# oresat-c3-prototype.net
KiCad netlist of a schematic drawn in EAGLE
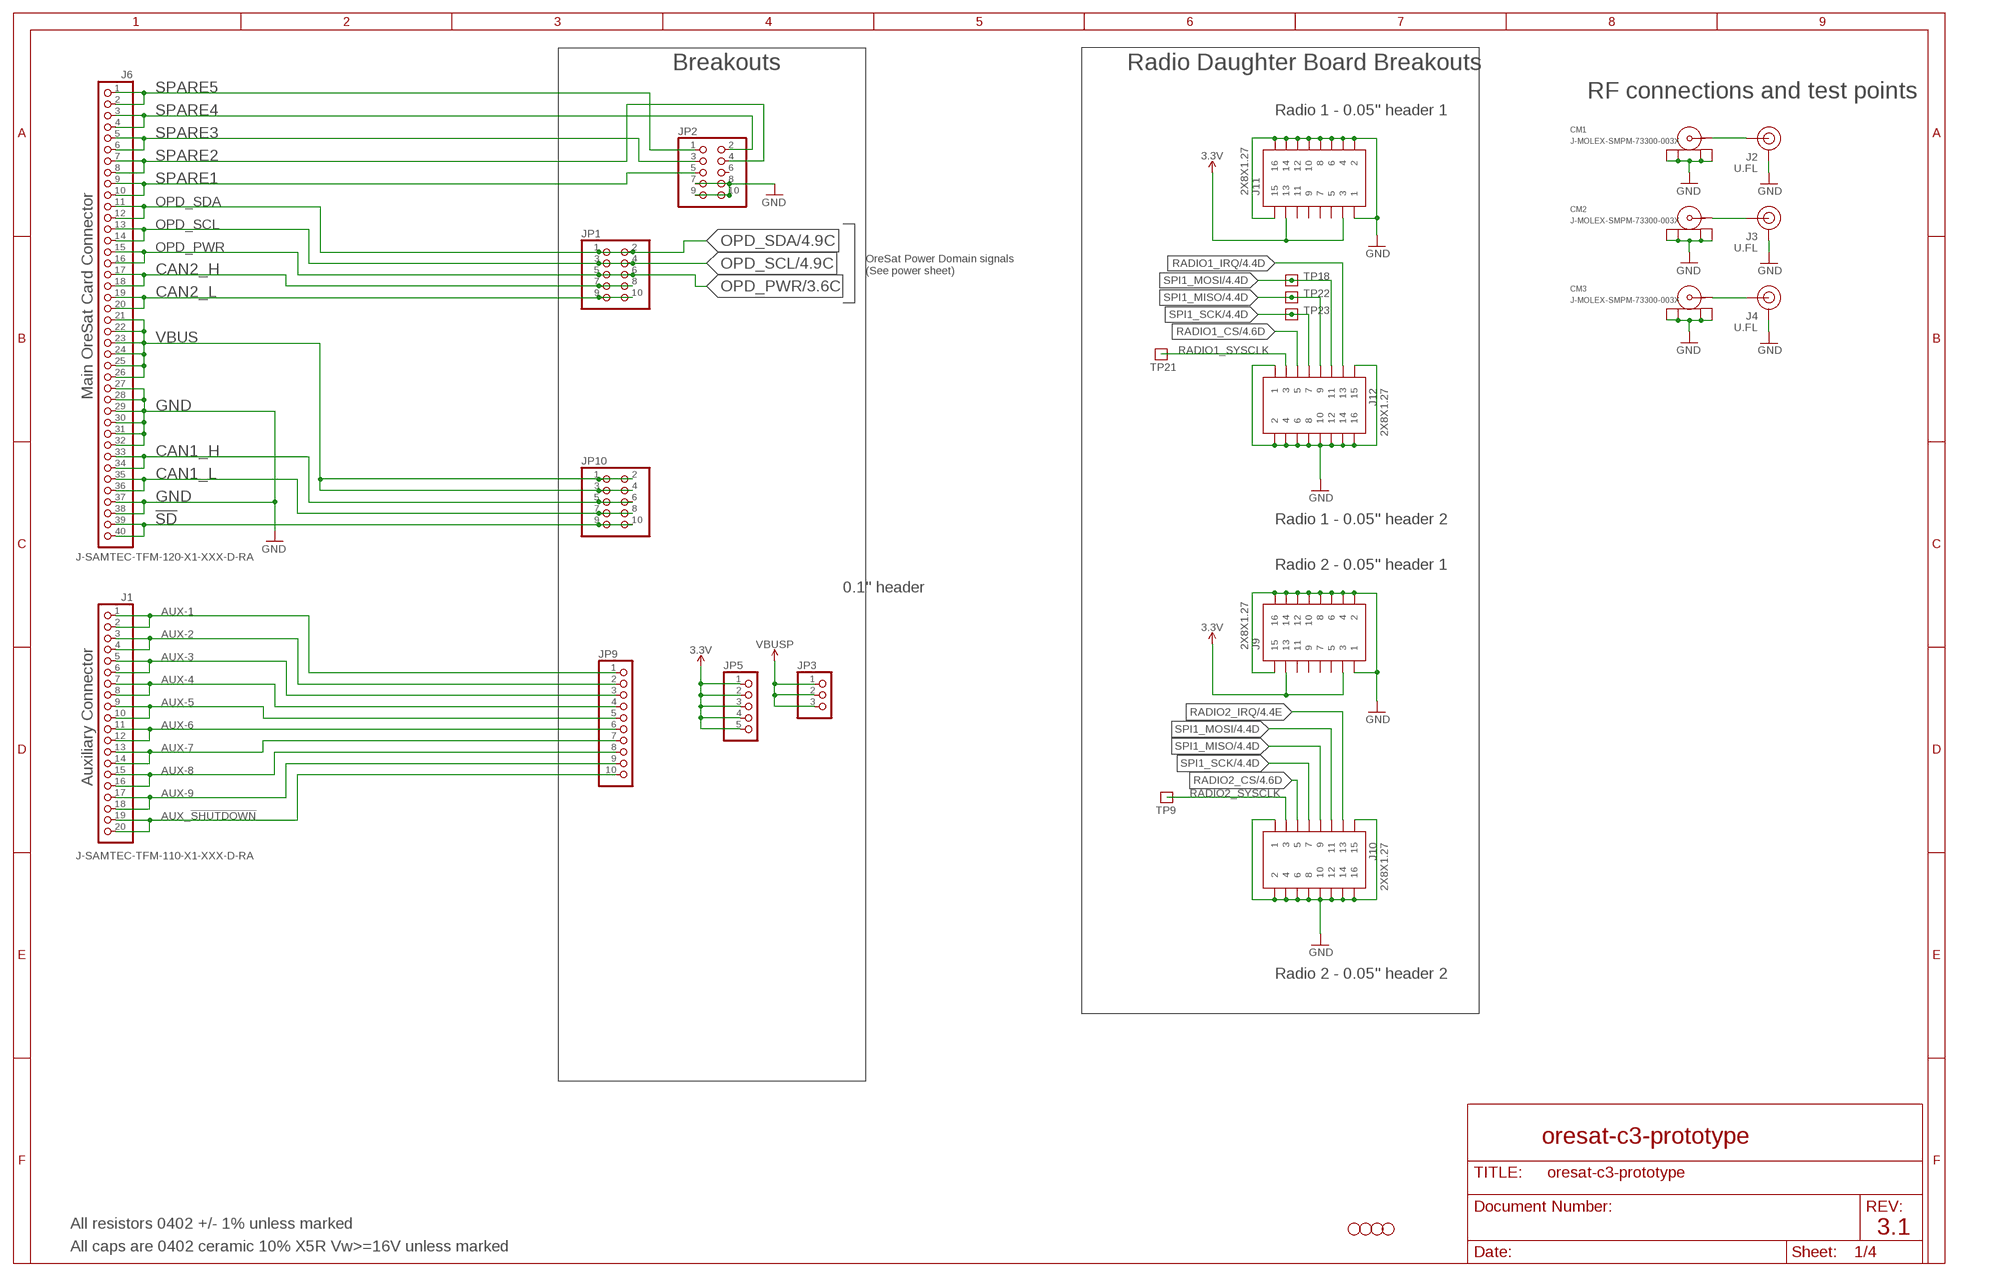
[diagram p0: schematic, sheet 1]
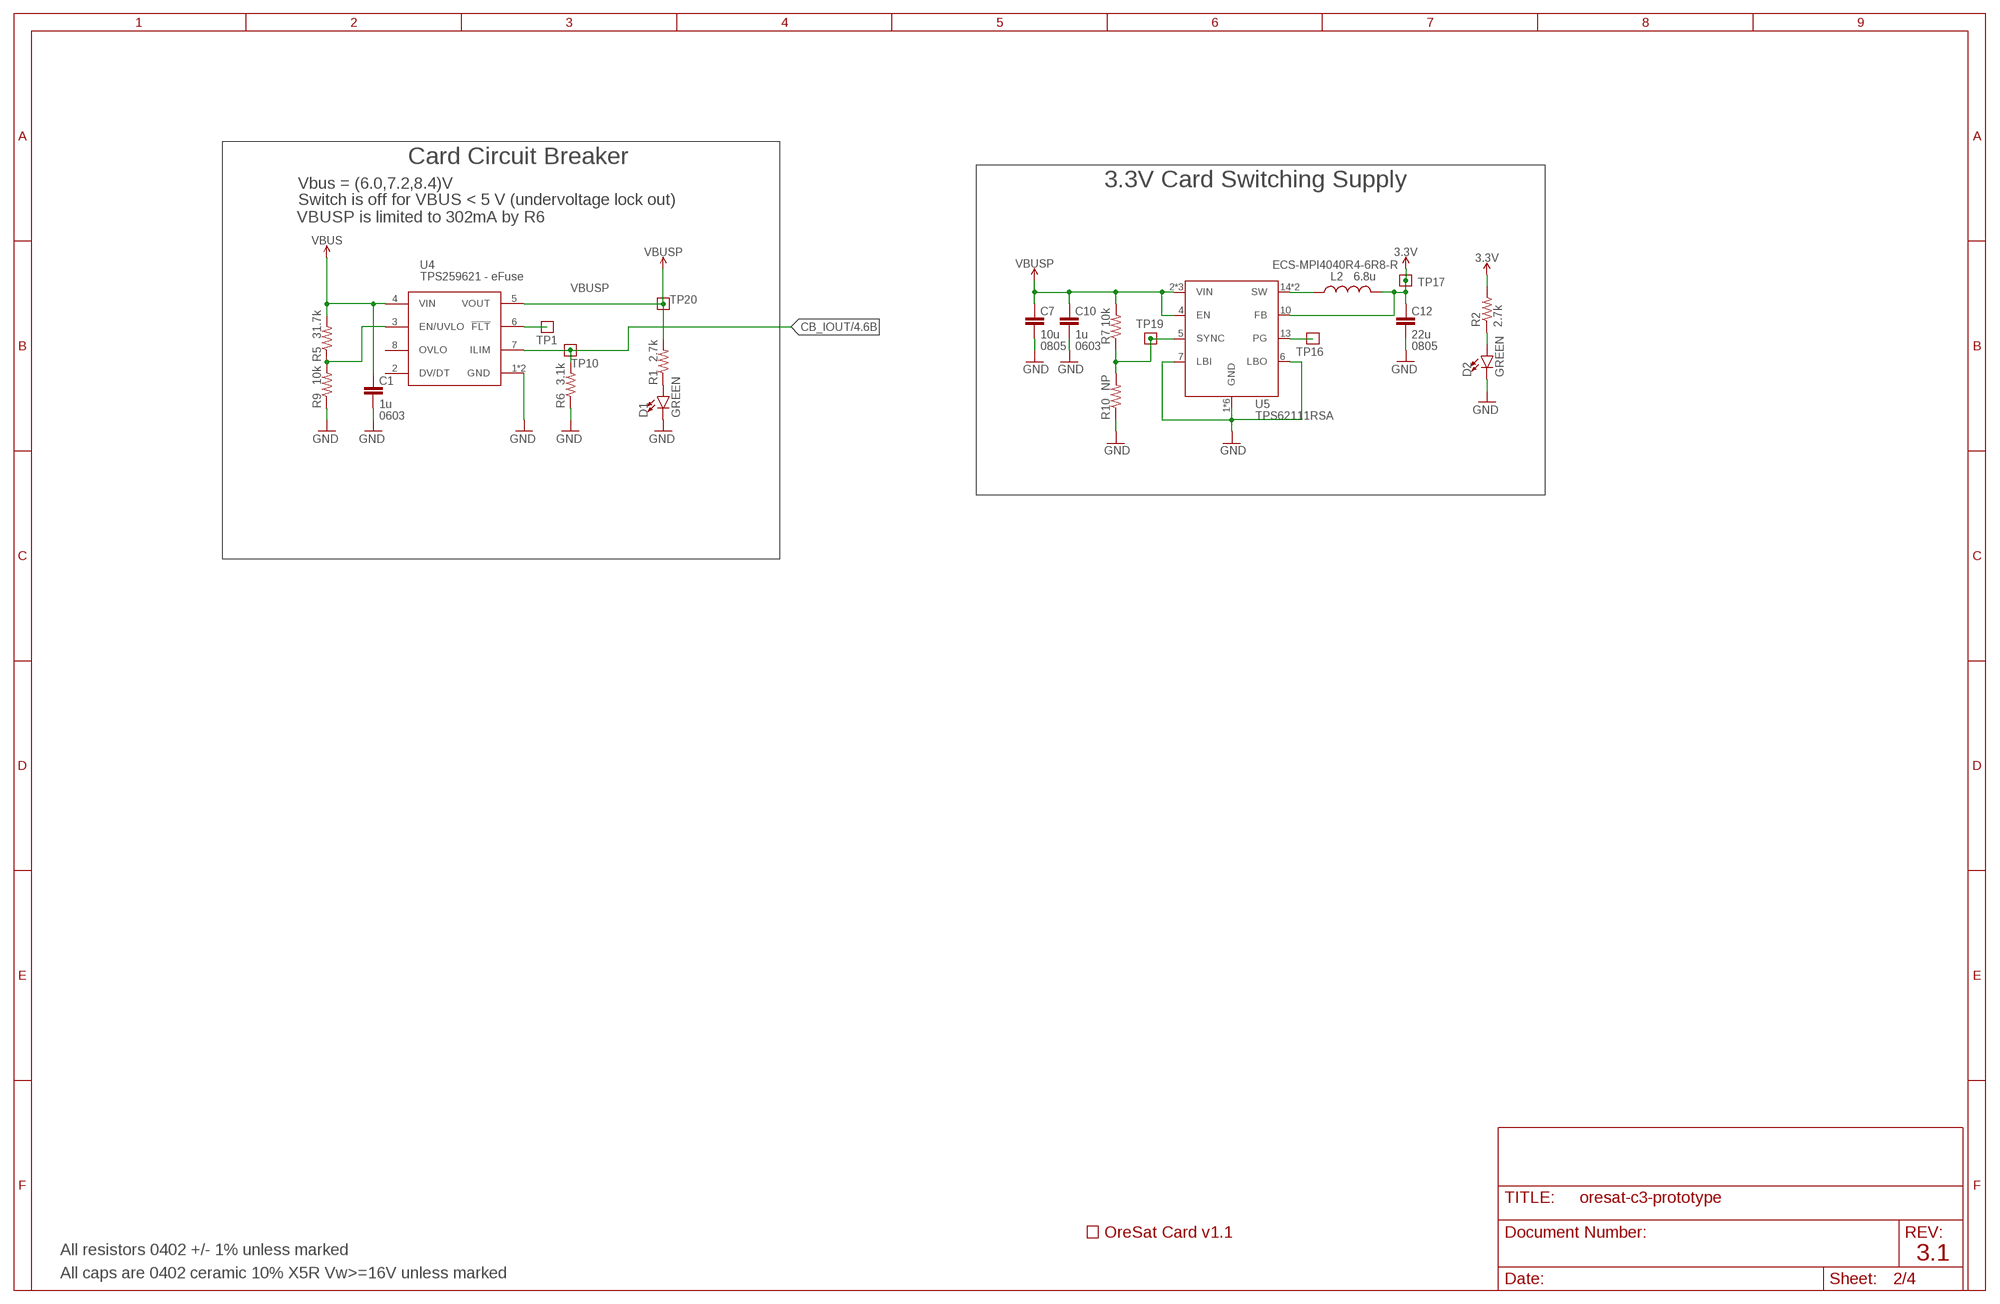
[diagram p1: schematic, sheet 2]
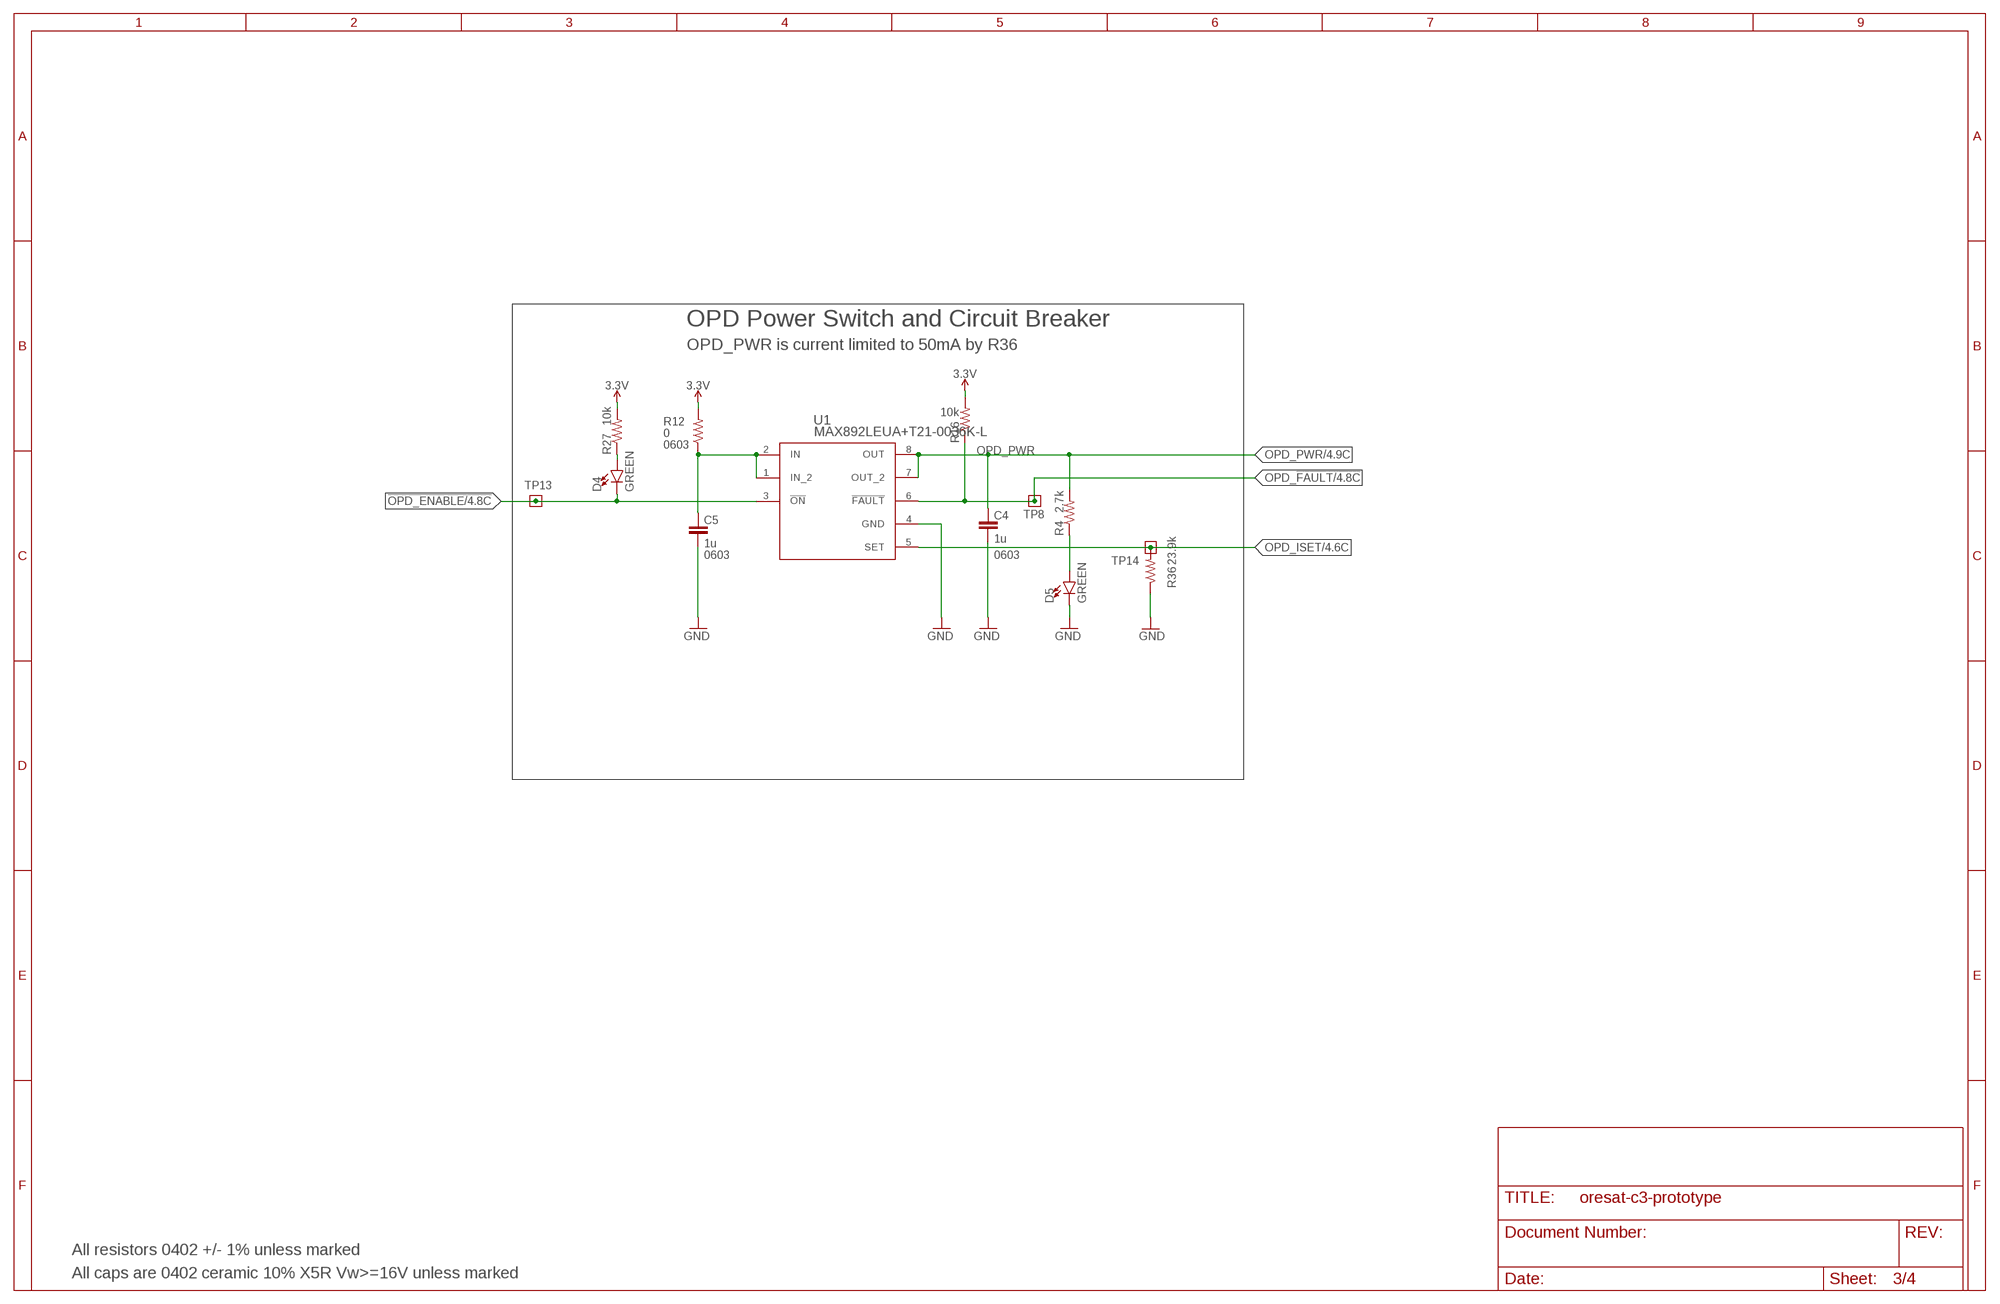
[diagram p2: schematic, sheet 3]
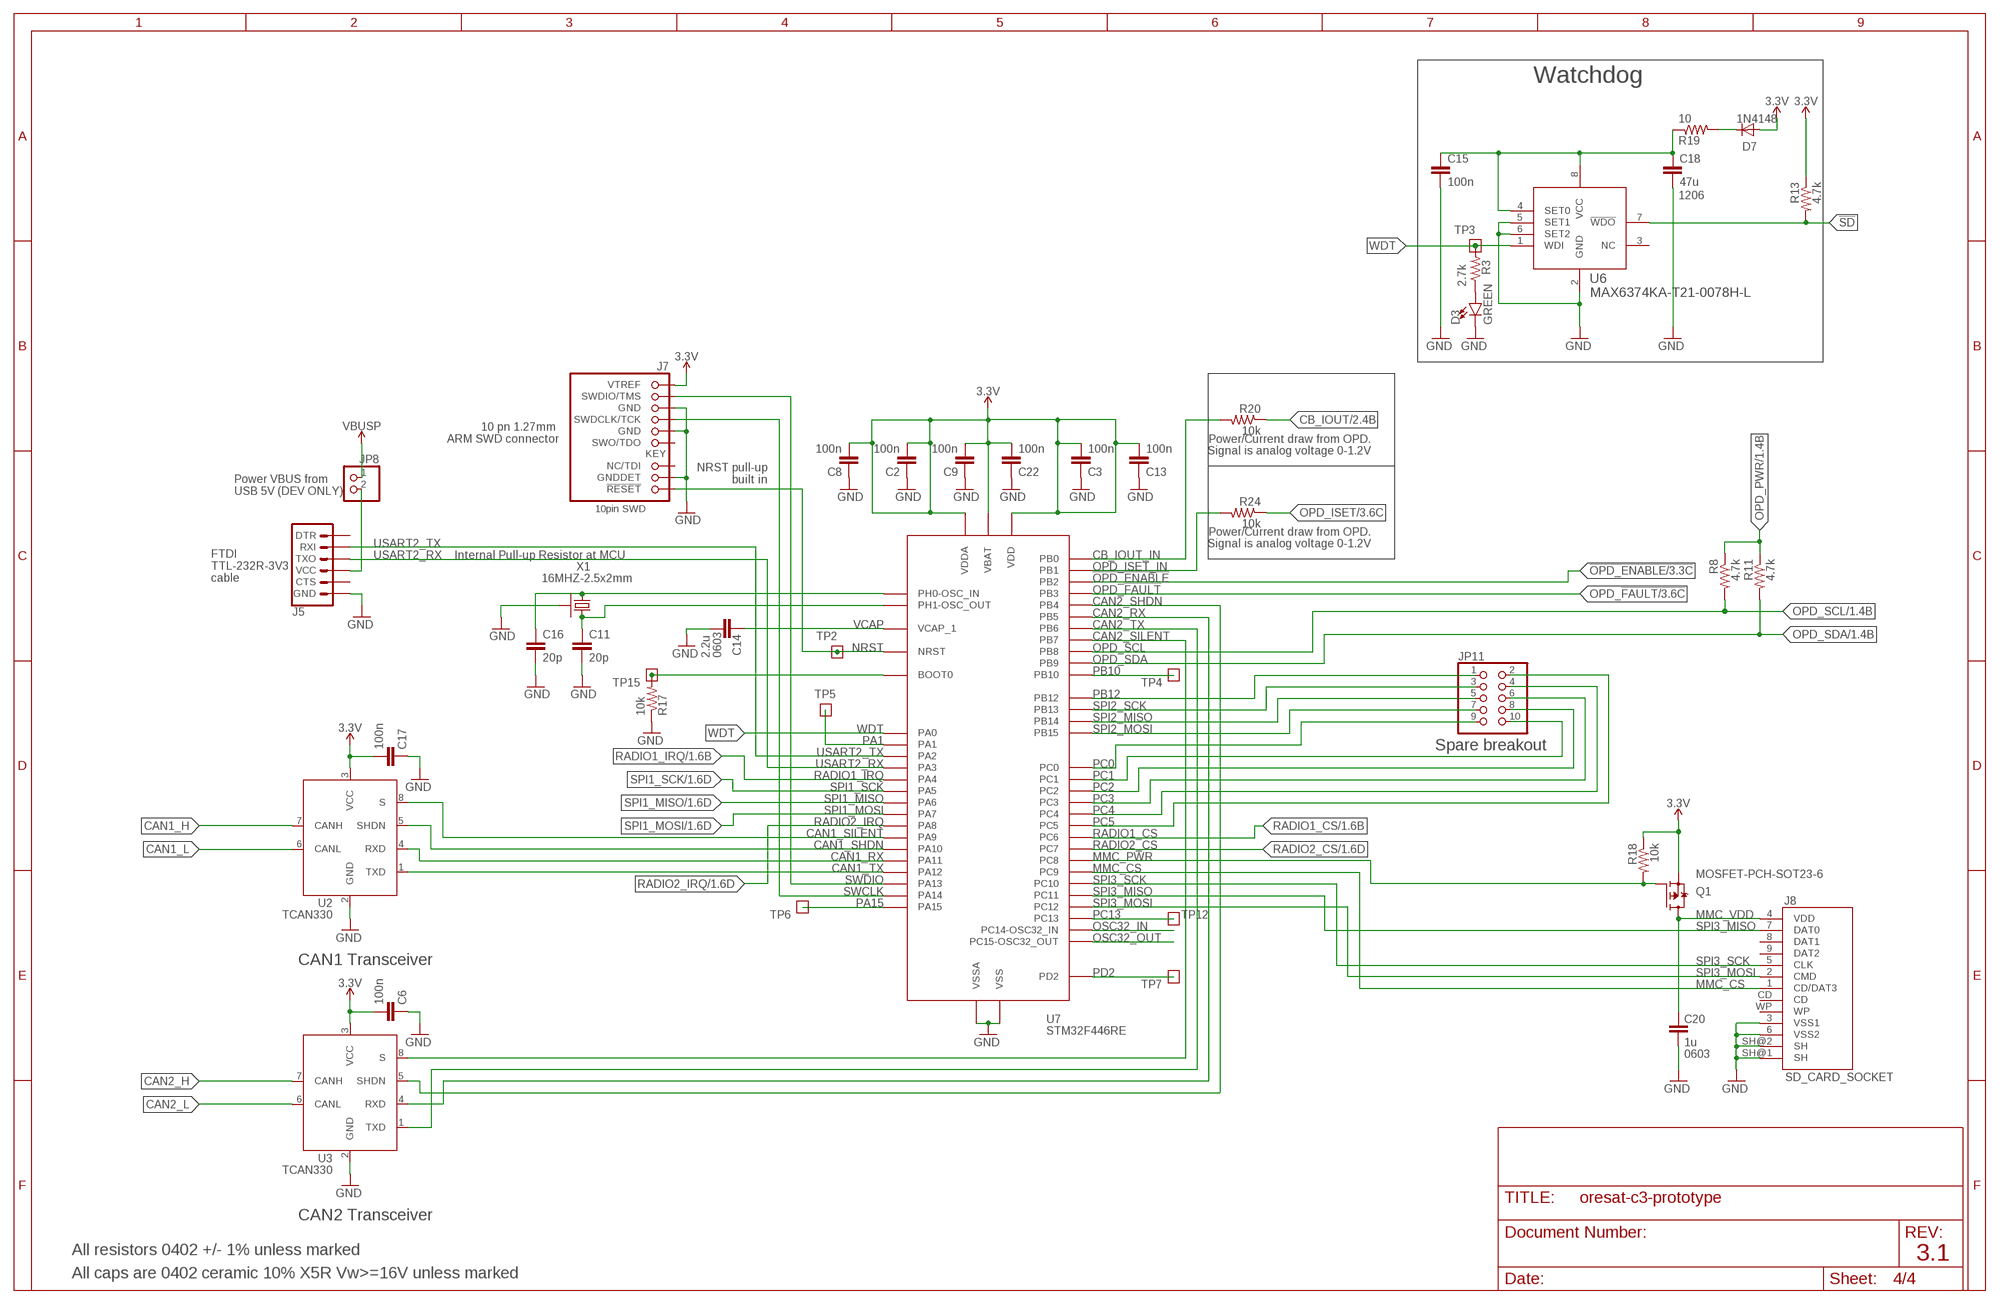
[diagram p3: schematic, sheet 4]

(export (version "E")
  (design (tool "Eeschema 10.0.6"))
  (components
    (comp (ref "C4")
      (value "1u")
      (footprint "eagle-import:.0603-B-NOSILK")
      (fields (field (name "MFR") "Samsung") (field (name "MPN") "CL05B104KO5NNNC"))
      (libsource (lib "eagle-import") (part "C-EU0603-B-NOSILK"))
    )
    (comp (ref "C5")
      (value "1u")
      (footprint "eagle-import:.0603-B-NOSILK")
      (fields (field (name "MFR") "Samsung") (field (name "MPN") "CL05B104KO5NNNC"))
      (libsource (lib "eagle-import") (part "C-EU0603-B-NOSILK"))
    )
    (comp (ref "D4")
      (value "GREEN")
      (footprint "eagle-import:LED-0603")
      (libsource (lib "eagle-import") (part "LED-GREEN0603"))
    )
    (comp (ref "D5")
      (value "GREEN")
      (footprint "eagle-import:LED-0603")
      (libsource (lib "eagle-import") (part "LED-GREEN0603"))
    )
    (comp (ref "R4")
      (value "2.7k")
      (footprint "eagle-import:.0402-B-NOSILK")
      (fields (field (name "MFR") "Samsung") (field (name "MPN") "RC1005F6653CS"))
      (libsource (lib "eagle-import") (part "R-US_0402-B-NOSILK"))
    )
    (comp (ref "R12")
      (value "0")
      (footprint "eagle-import:.0603-B-NOSILK")
      (fields (field (name "MFR") "Samsung") (field (name "MPN") "RC1005F6653CS"))
      (libsource (lib "eagle-import") (part "R-US_0603-B-NOSILK"))
    )
    (comp (ref "R16")
      (value "10k")
      (footprint "eagle-import:.0402-B-NOSILK")
      (fields (field (name "MFR") "Samsung") (field (name "MPN") "RC1005F6653CS"))
      (libsource (lib "eagle-import") (part "R-US_0402-B-NOSILK"))
    )
    (comp (ref "R27")
      (value "10k")
      (footprint "eagle-import:.0402-B-NOSILK")
      (fields (field (name "MFR") "Samsung") (field (name "MPN") "RC1005F6653CS"))
      (libsource (lib "eagle-import") (part "R-US_0402-B-NOSILK"))
    )
    (comp (ref "R36")
      (value "23.9k")
      (footprint "eagle-import:.0402-B-NOSILK")
      (fields (field (name "MFR") "Samsung") (field (name "MPN") "RC1005F6653CS"))
      (libsource (lib "eagle-import") (part "R-US_0402-B-NOSILK"))
    )
    (comp (ref "TP8")
      (value "TEST-POINT")
      (footprint "eagle-import:2MM-TEST-POINT")
      (libsource (lib "eagle-import") (part "TEST-POINT"))
    )
    (comp (ref "TP13")
      (value "TEST-POINT")
      (footprint "eagle-import:2MM-TEST-POINT")
      (libsource (lib "eagle-import") (part "TEST-POINT"))
    )
    (comp (ref "TP14")
      (value "TEST-POINT")
      (footprint "eagle-import:2MM-TEST-POINT")
      (libsource (lib "eagle-import") (part "TEST-POINT"))
    )
    (comp (ref "U1")
      (value "MAX892LEUA+T21-0036K-L")
      (footprint "eagle-import:21-0036K-L")
      (fields (field (name "MANUFACTURER_PART_NUMBER") "MAX892LEUA+T"))
      (libsource (lib "eagle-import") (part "MAX892LEUA+T21-0036K-L"))
    )
    (comp (ref "C2")
      (value "100n")
      (footprint "eagle-import:.0402-B-NOSILK")
      (fields (field (name "MFR") "Samsung") (field (name "MPN") "CL05B104KO5NNNC"))
      (libsource (lib "eagle-import") (part "C-EU0402-B-NOSILK"))
    )
    (comp (ref "C3")
      (value "100n")
      (footprint "eagle-import:.0402-B-NOSILK")
      (fields (field (name "MFR") "Samsung") (field (name "MPN") "CL05B104KO5NNNC"))
      (libsource (lib "eagle-import") (part "C-EU0402-B-NOSILK"))
    )
    (comp (ref "C6")
      (value "100n")
      (footprint "eagle-import:.0402-B-NOSILK")
      (fields (field (name "MFR") "Samsung") (field (name "MPN") "CL05B104KO5NNNC"))
      (libsource (lib "eagle-import") (part "C-EU0402-B-NOSILK"))
    )
    (comp (ref "C8")
      (value "100n")
      (footprint "eagle-import:.0402-B-NOSILK")
      (fields (field (name "MFR") "Samsung") (field (name "MPN") "CL05B104KO5NNNC"))
      (libsource (lib "eagle-import") (part "C-EU0402-B-NOSILK"))
    )
    (comp (ref "C9")
      (value "100n")
      (footprint "eagle-import:.0402-B-NOSILK")
      (fields (field (name "MFR") "Samsung") (field (name "MPN") "CL05B104KO5NNNC"))
      (libsource (lib "eagle-import") (part "C-EU0402-B-NOSILK"))
    )
    (comp (ref "C11")
      (value "20p")
      (footprint "eagle-import:.0402-B-NOSILK")
      (fields (field (name "MFR") "Samsung") (field (name "MPN") "CL05C200JB51PNC"))
      (libsource (lib "eagle-import") (part "rcl_custom_C-EU0402-B-NOSILK"))
    )
    (comp (ref "C13")
      (value "100n")
      (footprint "eagle-import:.0402-B-NOSILK")
      (fields (field (name "MFR") "Samsung") (field (name "MPN") "CL05B104KO5NNNC"))
      (libsource (lib "eagle-import") (part "C-EU0402-B-NOSILK"))
    )
    (comp (ref "C14")
      (value "2.2u")
      (footprint "eagle-import:.0603-B-NOSILK")
      (fields (field (name "MFR") "Samsung") (field (name "MPN") "CL05B104KO5NNNC"))
      (libsource (lib "eagle-import") (part "C-EU0603-B-NOSILK"))
    )
    (comp (ref "C15")
      (value "100n")
      (footprint "eagle-import:.0402-B-NOSILK")
      (fields (field (name "MFR") "Samsung") (field (name "MPN") "CL05C200JB51PNC"))
      (libsource (lib "eagle-import") (part "C-EU0402-B-NOSILK"))
    )
    (comp (ref "C16")
      (value "20p")
      (footprint "eagle-import:.0402-B-NOSILK")
      (fields (field (name "MFR") "Samsung") (field (name "MPN") "CL05C200JB51PNC"))
      (libsource (lib "eagle-import") (part "C-EU0402-B-NOSILK"))
    )
    (comp (ref "C17")
      (value "100n")
      (footprint "eagle-import:.0402-B-NOSILK")
      (fields (field (name "MFR") "Samsung") (field (name "MPN") "CL05B104KO5NNNC"))
      (libsource (lib "eagle-import") (part "C-EU0402-B-NOSILK"))
    )
    (comp (ref "C18")
      (value "47u")
      (footprint "eagle-import:1206-B")
      (fields (field (name "MFR") "Samsung") (field (name "MPN") "CL05C200JB51PNC"))
      (libsource (lib "eagle-import") (part "C-EU1206-B"))
    )
    (comp (ref "C20")
      (value "1u")
      (footprint "eagle-import:.0603-B-NOSILK")
      (fields (field (name "MFR") "Samsung") (field (name "MPN") "CL05B104KO5NNNC"))
      (libsource (lib "eagle-import") (part "C-EU0603-B-NOSILK"))
    )
    (comp (ref "C22")
      (value "100n")
      (footprint "eagle-import:.0402-B-NOSILK")
      (fields (field (name "MFR") "Samsung") (field (name "MPN") "CL05B104KO5NNNC"))
      (libsource (lib "eagle-import") (part "C-EU0402-B-NOSILK"))
    )
    (comp (ref "D3")
      (value "GREEN")
      (footprint "eagle-import:LED-0603")
      (libsource (lib "eagle-import") (part "LED-GREEN0603"))
    )
    (comp (ref "D7")
      (value "1N4148")
      (footprint "eagle-import:SOD-323")
      (libsource (lib "eagle-import") (part "DIODESOD"))
    )
    (comp (ref "J5")
      (value "6_PIN_SERIAL_TARGETSILK")
      (footprint "eagle-import:6_PIN_SERIAL_TARGET_SIDE_W_SILK")
      (libsource (lib "eagle-import") (part "6_PIN_SERIAL_TARGETSILK"))
    )
    (comp (ref "J7")
      (value "FTSH-105-XX-X-DV-K")
      (footprint "eagle-import:CON10_2X5_DUK_FTSH")
      (fields (field (name "MFR") "Samtec") (field (name "MPN") "FTSH-105-01-F-DV-K"))
      (libsource (lib "eagle-import") (part "FTSH-105-XX-X-DV-K"))
    )
    (comp (ref "J8")
      (value "SD_CARD_SOCKET")
      (footprint "eagle-import:SD")
      (libsource (lib "eagle-import") (part "SD_CARD_SOCKET"))
    )
    (comp (ref "JP8")
      (value "PINHD-1X2")
      (footprint "eagle-import:1X02")
      (libsource (lib "eagle-import") (part "PINHD-1X2"))
    )
    (comp (ref "JP11")
      (value "PINHD-2X5")
      (footprint "eagle-import:2X05")
      (libsource (lib "eagle-import") (part "PINHD-2X5"))
    )
    (comp (ref "Q1")
      (value "MOSFET-PCH-SOT23-6")
      (footprint "eagle-import:SOT23-6")
      (libsource (lib "eagle-import") (part "MOSFET-PCH-SOT23-6"))
    )
    (comp (ref "R3")
      (value "2.7k")
      (footprint "eagle-import:.0402-B-NOSILK")
      (fields (field (name "MFR") "Samsung") (field (name "MPN") "RC1005F6653CS"))
      (libsource (lib "eagle-import") (part "R-US_0402-B-NOSILK"))
    )
    (comp (ref "R8")
      (value "4.7k")
      (footprint "eagle-import:.0402-B-NOSILK")
      (libsource (lib "eagle-import") (part "R-US_0402-B-NOSILK"))
    )
    (comp (ref "R11")
      (value "4.7k")
      (footprint "eagle-import:.0402-B-NOSILK")
      (libsource (lib "eagle-import") (part "R-US_0402-B-NOSILK"))
    )
    (comp (ref "R13")
      (value "4.7k")
      (footprint "eagle-import:.0402-B-NOSILK")
      (libsource (lib "eagle-import") (part "R-US_0402-B-NOSILK"))
    )
    (comp (ref "R17")
      (value "10k")
      (footprint "eagle-import:.0402-B-NOSILK")
      (fields (field (name "MFR") "Samsung") (field (name "MPN") "RC1005F6653CS"))
      (libsource (lib "eagle-import") (part "R-US_0402-B-NOSILK"))
    )
    (comp (ref "R18")
      (value "10k")
      (footprint "eagle-import:.0402-B-NOSILK")
      (libsource (lib "eagle-import") (part "R-US_0402-B-NOSILK"))
    )
    (comp (ref "R19")
      (value "10")
      (footprint "eagle-import:.0402-B-NOSILK")
      (libsource (lib "eagle-import") (part "R-US_0402-B-NOSILK"))
    )
    (comp (ref "R20")
      (value "10k")
      (footprint "eagle-import:.0402-B-NOSILK")
      (libsource (lib "eagle-import") (part "R-US_0402-B-NOSILK"))
    )
    (comp (ref "R24")
      (value "10k")
      (footprint "eagle-import:.0402-B-NOSILK")
      (libsource (lib "eagle-import") (part "R-US_0402-B-NOSILK"))
    )
    (comp (ref "TP2")
      (value "TEST-POINT")
      (footprint "eagle-import:2MM-TEST-POINT")
      (libsource (lib "eagle-import") (part "TEST-POINT"))
    )
    (comp (ref "TP3")
      (value "TEST-POINT")
      (footprint "eagle-import:2MM-TEST-POINT")
      (libsource (lib "eagle-import") (part "TEST-POINT"))
    )
    (comp (ref "TP4")
      (value "TEST-POINT")
      (footprint "eagle-import:2MM-TEST-POINT")
      (libsource (lib "eagle-import") (part "TEST-POINT"))
    )
    (comp (ref "TP5")
      (value "TEST-POINT")
      (footprint "eagle-import:2MM-TEST-POINT")
      (libsource (lib "eagle-import") (part "TEST-POINT"))
    )
    (comp (ref "TP6")
      (value "TEST-POINT")
      (footprint "eagle-import:2MM-TEST-POINT")
      (libsource (lib "eagle-import") (part "TEST-POINT"))
    )
    (comp (ref "TP7")
      (value "TEST-POINT")
      (footprint "eagle-import:2MM-TEST-POINT")
      (libsource (lib "eagle-import") (part "TEST-POINT"))
    )
    (comp (ref "TP12")
      (value "TEST-POINT")
      (footprint "eagle-import:2MM-TEST-POINT")
      (libsource (lib "eagle-import") (part "TEST-POINT"))
    )
    (comp (ref "TP15")
      (value "TEST-POINT")
      (footprint "eagle-import:2MM-TEST-POINT")
      (libsource (lib "eagle-import") (part "TEST-POINT"))
    )
    (comp (ref "U2")
      (value "TCAN330")
      (footprint "eagle-import:SOT23-8_TI-DCN")
      (fields (field (name "MFR") "Texas Instruments") (field (name "MPN") "TCAN330GDCNT"))
      (libsource (lib "eagle-import") (part "TCAN330"))
    )
    (comp (ref "U3")
      (value "TCAN330")
      (footprint "eagle-import:SOT23-8_TI-DCN")
      (fields (field (name "MFR") "Texas Instruments") (field (name "MPN") "TCAN330GDCNT"))
      (libsource (lib "eagle-import") (part "TCAN330"))
    )
    (comp (ref "U6")
      (value "MAX6374KA-T21-0078H-L")
      (footprint "eagle-import:21-0078H-L")
      (fields (field (name "MANUFACTURER_PART_NUMBER") "max6374kat"))
      (libsource (lib "eagle-import") (part "MAX6374KA-T21-0078H-L"))
    )
    (comp (ref "U7")
      (value "STM32F446RE")
      (footprint "eagle-import:QFP-10X10-64")
      (libsource (lib "eagle-import") (part "STM32F446RE"))
    )
    (comp (ref "X1")
      (value "16MHZ-2.5x2mm")
      (footprint "eagle-import:CRYSTAL_2.5X2")
      (fields (field (name "MFR") "ECS Inc.") (field (name "MPN") "ECS-160-10-36Q-ES-TR"))
      (libsource (lib "eagle-import") (part "CRYSTAL-WITH-GND"))
    )
    (comp (ref "CM1")
      (value "J-MOLEX-SMPM-73300-003X")
      (footprint "eagle-import:J-MOLEX-SMPM-073300-003X")
      (fields (field (name "MFR") "Molex") (field (name "MPN") "73300-0020"))
      (libsource (lib "eagle-import") (part "J-MOLEX-SMPM-73300-003X"))
    )
    (comp (ref "CM2")
      (value "J-MOLEX-SMPM-73300-003X")
      (footprint "eagle-import:J-MOLEX-SMPM-073300-003X")
      (fields (field (name "MFR") "Molex") (field (name "MPN") "73300-0020"))
      (libsource (lib "eagle-import") (part "J-MOLEX-SMPM-73300-003X"))
    )
    (comp (ref "CM3")
      (value "J-MOLEX-SMPM-73300-003X")
      (footprint "eagle-import:J-MOLEX-SMPM-073300-003X")
      (fields (field (name "MFR") "Molex") (field (name "MPN") "73300-0020"))
      (libsource (lib "eagle-import") (part "J-MOLEX-SMPM-73300-003X"))
    )
    (comp (ref "H1")
      (value "STAND-OFFTIGHT")
      (footprint "eagle-import:STAND-OFF-TIGHT")
      (libsource (lib "eagle-import") (part "STAND-OFFTIGHT"))
    )
    (comp (ref "H2")
      (value "STAND-OFFTIGHT")
      (footprint "eagle-import:STAND-OFF-TIGHT")
      (libsource (lib "eagle-import") (part "STAND-OFFTIGHT"))
    )
    (comp (ref "H3")
      (value "STAND-OFFTIGHT")
      (footprint "eagle-import:STAND-OFF-TIGHT")
      (libsource (lib "eagle-import") (part "STAND-OFFTIGHT"))
    )
    (comp (ref "H4")
      (value "STAND-OFFTIGHT")
      (footprint "eagle-import:STAND-OFF-TIGHT")
      (libsource (lib "eagle-import") (part "STAND-OFFTIGHT"))
    )
    (comp (ref "J1")
      (value "J-SAMTEC-TFM-110-X1-XXX-D-RA")
      (footprint "eagle-import:J-SAMTEC-TFM-110-X1-XXX-D-RA")
      (fields (field (name "MFR") "Samtec") (field (name "MPN") "TFM-110-01-L-D-RA "))
      (libsource (lib "eagle-import") (part "J-SAMTEC-TFM-110-X1-XXX-D-RA"))
    )
    (comp (ref "J2")
      (value "U.FL")
      (footprint "eagle-import:U.FL")
      (libsource (lib "eagle-import") (part "U.FL2PIN"))
    )
    (comp (ref "J3")
      (value "U.FL")
      (footprint "eagle-import:U.FL")
      (libsource (lib "eagle-import") (part "U.FL2PIN"))
    )
    (comp (ref "J4")
      (value "U.FL")
      (footprint "eagle-import:U.FL")
      (libsource (lib "eagle-import") (part "U.FL2PIN"))
    )
    (comp (ref "J6")
      (value "J-SAMTEC-TFM-120-X1-XXX-D-RA")
      (footprint "eagle-import:J-SAMTEC-TFM-120-X1-XXX-D-RA")
      (fields (field (name "MFR") "Samtec") (field (name "MPN") "TFM-120-01-L-D-RA"))
      (libsource (lib "eagle-import") (part "J-SAMTEC-TFM-120-X1-XXX-D-RA"))
    )
    (comp (ref "J9")
      (value "2X8X1.27")
      (footprint "eagle-import:2X8X1.27")
      (libsource (lib "eagle-import") (part "2X8X1.27"))
    )
    (comp (ref "J10")
      (value "2X8X1.27")
      (footprint "eagle-import:2X8X1.27")
      (libsource (lib "eagle-import") (part "2X8X1.27"))
    )
    (comp (ref "J11")
      (value "2X8X1.27")
      (footprint "eagle-import:2X8X1.27")
      (libsource (lib "eagle-import") (part "2X8X1.27"))
    )
    (comp (ref "J12")
      (value "2X8X1.27")
      (footprint "eagle-import:2X8X1.27")
      (libsource (lib "eagle-import") (part "2X8X1.27"))
    )
    (comp (ref "JP1")
      (value "PINHD-2X5")
      (footprint "eagle-import:2X05")
      (libsource (lib "eagle-import") (part "PINHD-2X5"))
    )
    (comp (ref "JP2")
      (value "PINHD-2X5")
      (footprint "eagle-import:2X05")
      (libsource (lib "eagle-import") (part "PINHD-2X5"))
    )
    (comp (ref "JP3")
      (value "PINHD-1X3")
      (footprint "eagle-import:1X03")
      (libsource (lib "eagle-import") (part "PINHD-1X3"))
    )
    (comp (ref "JP5")
      (value "PINHD-1X5")
      (footprint "eagle-import:1X05")
      (libsource (lib "eagle-import") (part "PINHD-1X5"))
    )
    (comp (ref "JP9")
      (value "PINHD-1X10")
      (footprint "eagle-import:1X10")
      (libsource (lib "eagle-import") (part "PINHD-1X10"))
    )
    (comp (ref "JP10")
      (value "PINHD-2X5")
      (footprint "eagle-import:2X05")
      (libsource (lib "eagle-import") (part "PINHD-2X5"))
    )
    (comp (ref "TP9")
      (value "TEST-POINT")
      (footprint "eagle-import:2MM-TEST-POINT")
      (libsource (lib "eagle-import") (part "TEST-POINT"))
    )
    (comp (ref "TP18")
      (value "TEST-POINT")
      (footprint "eagle-import:2MM-TEST-POINT")
      (libsource (lib "eagle-import") (part "TEST-POINT"))
    )
    (comp (ref "TP21")
      (value "TEST-POINT")
      (footprint "eagle-import:2MM-TEST-POINT")
      (libsource (lib "eagle-import") (part "TEST-POINT"))
    )
    (comp (ref "TP22")
      (value "TEST-POINT")
      (footprint "eagle-import:2MM-TEST-POINT")
      (libsource (lib "eagle-import") (part "TEST-POINT"))
    )
    (comp (ref "TP23")
      (value "TEST-POINT")
      (footprint "eagle-import:2MM-TEST-POINT")
      (libsource (lib "eagle-import") (part "TEST-POINT"))
    )
    (comp (ref "C1")
      (value "1u")
      (footprint "eagle-import:.0603-B-NOSILK")
      (fields (field (name "MFR") "Samsung") (field (name "MPN") "CL05B104KO5NNNC"))
      (libsource (lib "eagle-import") (part "C-EU0603-B-NOSILK"))
    )
    (comp (ref "C7")
      (value "10u")
      (footprint "eagle-import:.0805-B-NOSILK")
      (libsource (lib "eagle-import") (part "C-EU0805-B-NOSILK"))
    )
    (comp (ref "C10")
      (value "1u")
      (footprint "eagle-import:.0603-B-NOSILK")
      (fields (field (name "MFR") "Samsung") (field (name "MPN") "CL05B104KO5NNNC"))
      (libsource (lib "eagle-import") (part "C-EU0603-B-NOSILK"))
    )
    (comp (ref "C12")
      (value "22u")
      (footprint "eagle-import:.0805-B-NOSILK")
      (libsource (lib "eagle-import") (part "C-EU0805-B-NOSILK"))
    )
    (comp (ref "D1")
      (value "GREEN")
      (footprint "eagle-import:LED-0603")
      (libsource (lib "eagle-import") (part "LED-GREEN0603"))
    )
    (comp (ref "D2")
      (value "GREEN")
      (footprint "eagle-import:LED-0603")
      (libsource (lib "eagle-import") (part "LED-GREEN0603"))
    )
    (comp (ref "L2")
      (value "6.8u")
      (footprint "eagle-import:ECS-MPI4040")
      (fields (field (name "MFR") "ECS") (field (name "MPN") "ECS-MPI4040R4-6R8-R"))
      (libsource (lib "eagle-import") (part "L-ECS-MPI4040"))
    )
    (comp (ref "R1")
      (value "2.7k")
      (footprint "eagle-import:.0402-B-NOSILK")
      (fields (field (name "MFR") "Samsung") (field (name "MPN") "RC1005F6653CS"))
      (libsource (lib "eagle-import") (part "R-US_0402-B-NOSILK"))
    )
    (comp (ref "R2")
      (value "2.7k")
      (footprint "eagle-import:.0402-B-NOSILK")
      (fields (field (name "MFR") "Samsung") (field (name "MPN") "RC1005F6653CS"))
      (libsource (lib "eagle-import") (part "R-US_0402-B-NOSILK"))
    )
    (comp (ref "R5")
      (value "31.7k")
      (footprint "eagle-import:.0402-B-NOSILK")
      (fields (field (name "MFR") "Samsung") (field (name "MPN") "RC1005F6653CS"))
      (libsource (lib "eagle-import") (part "R-US_0402-B-NOSILK"))
    )
    (comp (ref "R6")
      (value "3.1k")
      (footprint "eagle-import:.0402-B-NOSILK")
      (fields (field (name "MFR") "Samsung") (field (name "MPN") "RC1005F6653CS"))
      (libsource (lib "eagle-import") (part "R-US_0402-B-NOSILK"))
    )
    (comp (ref "R7")
      (value "10k")
      (footprint "eagle-import:.0402-B-NOSILK")
      (fields (field (name "MFR") "Samsung") (field (name "MPN") "RC1005F6653CS"))
      (libsource (lib "eagle-import") (part "R-US_0402-B-NOSILK"))
    )
    (comp (ref "R9")
      (value "10k")
      (footprint "eagle-import:.0402-B-NOSILK")
      (fields (field (name "MFR") "Samsung") (field (name "MPN") "RC1005F6653CS"))
      (libsource (lib "eagle-import") (part "R-US_0402-B-NOSILK"))
    )
    (comp (ref "R10")
      (value "NP")
      (footprint "eagle-import:.0402-B-NOSILK")
      (fields (field (name "MFR") "Samsung") (field (name "MPN") "RC1005F6653CS"))
      (libsource (lib "eagle-import") (part "R-US_0402-B-NOSILK"))
    )
    (comp (ref "TP1")
      (value "TEST-POINT")
      (footprint "eagle-import:2MM-TEST-POINT")
      (libsource (lib "eagle-import") (part "TEST-POINT"))
    )
    (comp (ref "TP10")
      (value "TEST-POINT")
      (footprint "eagle-import:2MM-TEST-POINT")
      (libsource (lib "eagle-import") (part "TEST-POINT"))
    )
    (comp (ref "TP16")
      (value "TEST-POINT")
      (footprint "eagle-import:2MM-TEST-POINT")
      (libsource (lib "eagle-import") (part "TEST-POINT"))
    )
    (comp (ref "TP17")
      (value "TEST-POINT")
      (footprint "eagle-import:2MM-TEST-POINT")
      (libsource (lib "eagle-import") (part "TEST-POINT"))
    )
    (comp (ref "TP19")
      (value "TEST-POINT")
      (footprint "eagle-import:2MM-TEST-POINT")
      (libsource (lib "eagle-import") (part "TEST-POINT"))
    )
    (comp (ref "TP20")
      (value "TEST-POINT")
      (footprint "eagle-import:2MM-TEST-POINT")
      (libsource (lib "eagle-import") (part "TEST-POINT"))
    )
    (comp (ref "U$1")
      (value "ORESAT-CARD-V1.1-3XRF")
      (footprint "eagle-import:ORESAT-CARD-V1.1-3XRF")
      (libsource (lib "eagle-import") (part "ORESAT-CARD-V1.1-3XRF"))
    )
    (comp (ref "U4")
      (value "TPS259621 - eFuse")
      (footprint "eagle-import:SO-POWERPAD-8")
      (libsource (lib "eagle-import") (part "TPS2596XX"))
    )
    (comp (ref "U5")
      (value "TPS62111RSA")
      (footprint "eagle-import:S-PVQFN-16")
      (fields (field (name "MFR") "TI"))
      (libsource (lib "eagle-import") (part "TPS6211X"))
    )
  )
  (nets
    (net (code "1") (name "3.3V") (class "Default")
      (node (ref "C12") (pin "1") (pinfunction "1_1") (pintype "passive"))
      (node (ref "C13") (pin "2") (pinfunction "2_2") (pintype "passive"))
      (node (ref "C17") (pin "2") (pinfunction "2_2") (pintype "passive"))
      (node (ref "C2") (pin "2") (pinfunction "2_2") (pintype "passive"))
      (node (ref "C22") (pin "2") (pinfunction "2_2") (pintype "passive"))
      (node (ref "C3") (pin "2") (pinfunction "2_2") (pintype "passive"))
      (node (ref "C6") (pin "2") (pinfunction "2_2") (pintype "passive"))
      (node (ref "C8") (pin "2") (pinfunction "2_2") (pintype "passive"))
      (node (ref "C9") (pin "2") (pinfunction "2_2") (pintype "passive"))
      (node (ref "D7") (pin "2") (pinfunction "A_2") (pintype "passive"))
      (node (ref "J11") (pin "13") (pinfunction "13_13") (pintype "passive"))
      (node (ref "J11") (pin "3") (pinfunction "3_3") (pintype "passive"))
      (node (ref "J7") (pin "1") (pinfunction "VTREF_1") (pintype "passive"))
      (node (ref "J9") (pin "13") (pinfunction "13_13") (pintype "passive"))
      (node (ref "J9") (pin "3") (pinfunction "3_3") (pintype "passive"))
      (node (ref "JP5") (pin "1") (pinfunction "1_1") (pintype "passive"))
      (node (ref "JP5") (pin "2") (pinfunction "2_2") (pintype "passive"))
      (node (ref "JP5") (pin "3") (pinfunction "3_3") (pintype "passive"))
      (node (ref "JP5") (pin "4") (pinfunction "4_4") (pintype "passive"))
      (node (ref "JP5") (pin "5") (pinfunction "5_5") (pintype "passive"))
      (node (ref "L2") (pin "2") (pinfunction "2_2") (pintype "passive"))
      (node (ref "Q1") (pin "4") (pinfunction "S_4") (pintype "passive"))
      (node (ref "R12") (pin "2") (pinfunction "2_2") (pintype "passive"))
      (node (ref "R13") (pin "1") (pinfunction "1_1") (pintype "passive"))
      (node (ref "R16") (pin "2") (pinfunction "2_2") (pintype "passive"))
      (node (ref "R18") (pin "1") (pinfunction "1_1") (pintype "passive"))
      (node (ref "R2") (pin "2") (pinfunction "2_2") (pintype "passive"))
      (node (ref "R27") (pin "2") (pinfunction "2_2") (pintype "passive"))
      (node (ref "TP17") (pin "1") (pinfunction "1_1") (pintype "passive"))
      (node (ref "U2") (pin "3") (pinfunction "VCC_3") (pintype "power_in"))
      (node (ref "U3") (pin "3") (pinfunction "VCC_3") (pintype "power_in"))
      (node (ref "U5") (pin "10") (pinfunction "FB_10") (pintype "input"))
      (node (ref "U7") (pin "1") (pinfunction "VBAT_1") (pintype "power_in"))
      (node (ref "U7") (pin "13") (pinfunction "VDDA_13") (pintype "power_in"))
      (node (ref "U7") (pin "19") (pinfunction "VDD_19") (pintype "power_in"))
      (node (ref "U7") (pin "32") (pinfunction "VDD_32") (pintype "power_in"))
      (node (ref "U7") (pin "48") (pinfunction "VDD_48") (pintype "power_in"))
      (node (ref "U7") (pin "64") (pinfunction "VDD_64") (pintype "power_in"))
    )
    (net (code "2") (name "AUX-1") (class "Default")
      (node (ref "J1") (pin "1") (pinfunction "1_1") (pintype "passive"))
      (node (ref "J1") (pin "2") (pinfunction "2_2") (pintype "passive"))
      (node (ref "JP9") (pin "1") (pinfunction "1_1") (pintype "passive"))
    )
    (net (code "3") (name "AUX-2") (class "Default")
      (node (ref "J1") (pin "3") (pinfunction "3_3") (pintype "passive"))
      (node (ref "J1") (pin "4") (pinfunction "4_4") (pintype "passive"))
      (node (ref "JP9") (pin "2") (pinfunction "2_2") (pintype "passive"))
    )
    (net (code "4") (name "AUX-3") (class "Default")
      (node (ref "J1") (pin "5") (pinfunction "5_5") (pintype "passive"))
      (node (ref "J1") (pin "6") (pinfunction "6_6") (pintype "passive"))
      (node (ref "JP9") (pin "3") (pinfunction "3_3") (pintype "passive"))
    )
    (net (code "5") (name "AUX-4") (class "Default")
      (node (ref "J1") (pin "7") (pinfunction "7_7") (pintype "passive"))
      (node (ref "J1") (pin "8") (pinfunction "8_8") (pintype "passive"))
      (node (ref "JP9") (pin "4") (pinfunction "4_4") (pintype "passive"))
    )
    (net (code "6") (name "AUX-5") (class "Default")
      (node (ref "J1") (pin "10") (pinfunction "10_10") (pintype "passive"))
      (node (ref "J1") (pin "9") (pinfunction "9_9") (pintype "passive"))
      (node (ref "JP9") (pin "5") (pinfunction "5_5") (pintype "passive"))
    )
    (net (code "7") (name "AUX-6") (class "Default")
      (node (ref "J1") (pin "11") (pinfunction "11_11") (pintype "passive"))
      (node (ref "J1") (pin "12") (pinfunction "12_12") (pintype "passive"))
      (node (ref "JP9") (pin "6") (pinfunction "6_6") (pintype "passive"))
    )
    (net (code "8") (name "AUX-7") (class "Default")
      (node (ref "J1") (pin "13") (pinfunction "13_13") (pintype "passive"))
      (node (ref "J1") (pin "14") (pinfunction "14_14") (pintype "passive"))
      (node (ref "JP9") (pin "7") (pinfunction "7_7") (pintype "passive"))
    )
    (net (code "9") (name "AUX-8") (class "Default")
      (node (ref "J1") (pin "15") (pinfunction "15_15") (pintype "passive"))
      (node (ref "J1") (pin "16") (pinfunction "16_16") (pintype "passive"))
      (node (ref "JP9") (pin "8") (pinfunction "8_8") (pintype "passive"))
    )
    (net (code "10") (name "AUX-9") (class "Default")
      (node (ref "J1") (pin "17") (pinfunction "17_17") (pintype "passive"))
      (node (ref "J1") (pin "18") (pinfunction "18_18") (pintype "passive"))
      (node (ref "JP9") (pin "9") (pinfunction "9_9") (pintype "passive"))
    )
    (net (code "11") (name "AUX_~{SHUTDOWN}") (class "Default")
      (node (ref "J1") (pin "19") (pinfunction "19_19") (pintype "passive"))
      (node (ref "J1") (pin "20") (pinfunction "20_20") (pintype "passive"))
      (node (ref "JP9") (pin "10") (pinfunction "10_10") (pintype "passive"))
    )
    (net (code "12") (name "CAN1_H") (class "Default")
      (node (ref "J6") (pin "33") (pinfunction "33_33") (pintype "passive"))
      (node (ref "J6") (pin "34") (pinfunction "34_34") (pintype "passive"))
      (node (ref "JP10") (pin "5") (pinfunction "5_5") (pintype "passive"))
      (node (ref "JP10") (pin "6") (pinfunction "6_6") (pintype "passive"))
      (node (ref "U2") (pin "7") (pinfunction "CANH_7") (pintype "bidirectional"))
    )
    (net (code "13") (name "CAN1_L") (class "Default")
      (node (ref "J6") (pin "35") (pinfunction "35_35") (pintype "passive"))
      (node (ref "J6") (pin "36") (pinfunction "36_36") (pintype "passive"))
      (node (ref "JP10") (pin "7") (pinfunction "7_7") (pintype "passive"))
      (node (ref "JP10") (pin "8") (pinfunction "8_8") (pintype "passive"))
      (node (ref "U2") (pin "6") (pinfunction "CANL_6") (pintype "bidirectional"))
    )
    (net (code "14") (name "CAN1_RX") (class "Default")
      (node (ref "U2") (pin "4") (pinfunction "RXD_4") (pintype "output"))
      (node (ref "U7") (pin "44") (pinfunction "PA11_44") (pintype "bidirectional"))
    )
    (net (code "15") (name "CAN1_SHDN") (class "Default")
      (node (ref "U2") (pin "5") (pinfunction "SHDN_5") (pintype "input"))
      (node (ref "U7") (pin "43") (pinfunction "PA10_43") (pintype "bidirectional"))
    )
    (net (code "16") (name "CAN1_SILENT") (class "Default")
      (node (ref "U2") (pin "8") (pinfunction "S_8") (pintype "input"))
      (node (ref "U7") (pin "42") (pinfunction "PA9_42") (pintype "bidirectional"))
    )
    (net (code "17") (name "CAN1_TX") (class "Default")
      (node (ref "U2") (pin "1") (pinfunction "TXD_1") (pintype "input"))
      (node (ref "U7") (pin "45") (pinfunction "PA12_45") (pintype "bidirectional"))
    )
    (net (code "18") (name "CAN2_H") (class "Default")
      (node (ref "J6") (pin "17") (pinfunction "17_17") (pintype "passive"))
      (node (ref "J6") (pin "18") (pinfunction "18_18") (pintype "passive"))
      (node (ref "JP1") (pin "7") (pinfunction "7_7") (pintype "passive"))
      (node (ref "JP1") (pin "8") (pinfunction "8_8") (pintype "passive"))
      (node (ref "U3") (pin "7") (pinfunction "CANH_7") (pintype "bidirectional"))
    )
    (net (code "19") (name "CAN2_L") (class "Default")
      (node (ref "J6") (pin "19") (pinfunction "19_19") (pintype "passive"))
      (node (ref "J6") (pin "20") (pinfunction "20_20") (pintype "passive"))
      (node (ref "JP1") (pin "10") (pinfunction "10_10") (pintype "passive"))
      (node (ref "JP1") (pin "9") (pinfunction "9_9") (pintype "passive"))
      (node (ref "U3") (pin "6") (pinfunction "CANL_6") (pintype "bidirectional"))
    )
    (net (code "20") (name "CAN2_RX") (class "Default")
      (node (ref "U3") (pin "4") (pinfunction "RXD_4") (pintype "output"))
      (node (ref "U7") (pin "57") (pinfunction "PB5_57") (pintype "bidirectional"))
    )
    (net (code "21") (name "CAN2_SHDN") (class "Default")
      (node (ref "U3") (pin "5") (pinfunction "SHDN_5") (pintype "input"))
      (node (ref "U7") (pin "56") (pinfunction "PB4_56") (pintype "bidirectional"))
    )
    (net (code "22") (name "CAN2_SILENT") (class "Default")
      (node (ref "U3") (pin "8") (pinfunction "S_8") (pintype "input"))
      (node (ref "U7") (pin "59") (pinfunction "PB7_59") (pintype "bidirectional"))
    )
    (net (code "23") (name "CAN2_TX") (class "Default")
      (node (ref "U3") (pin "1") (pinfunction "TXD_1") (pintype "input"))
      (node (ref "U7") (pin "58") (pinfunction "PB6_58") (pintype "bidirectional"))
    )
    (net (code "24") (name "CB_IOUT") (class "Default")
      (node (ref "R20") (pin "1") (pinfunction "1_1") (pintype "passive"))
      (node (ref "R6") (pin "2") (pinfunction "2_2") (pintype "passive"))
      (node (ref "TP10") (pin "1") (pinfunction "1_1") (pintype "passive"))
      (node (ref "U4") (pin "7") (pinfunction "ILIM_7") (pintype "bidirectional"))
    )
    (net (code "25") (name "CB_IOUT_IN") (class "Default")
      (node (ref "R20") (pin "2") (pinfunction "2_2") (pintype "passive"))
      (node (ref "U7") (pin "26") (pinfunction "PB0_26") (pintype "bidirectional"))
    )
    (net (code "26") (name "GND") (class "Default")
      (node (ref "C1") (pin "2") (pinfunction "2_2") (pintype "passive"))
      (node (ref "C10") (pin "2") (pinfunction "2_2") (pintype "passive"))
      (node (ref "C11") (pin "2") (pinfunction "2_2") (pintype "passive"))
      (node (ref "C12") (pin "2") (pinfunction "2_2") (pintype "passive"))
      (node (ref "C13") (pin "1") (pinfunction "1_1") (pintype "passive"))
      (node (ref "C14") (pin "2") (pinfunction "2_2") (pintype "passive"))
      (node (ref "C15") (pin "2") (pinfunction "2_2") (pintype "passive"))
      (node (ref "C16") (pin "2") (pinfunction "2_2") (pintype "passive"))
      (node (ref "C17") (pin "1") (pinfunction "1_1") (pintype "passive"))
      (node (ref "C18") (pin "2") (pinfunction "2_2") (pintype "passive"))
      (node (ref "C2") (pin "1") (pinfunction "1_1") (pintype "passive"))
      (node (ref "C20") (pin "2") (pinfunction "2_2") (pintype "passive"))
      (node (ref "C22") (pin "1") (pinfunction "1_1") (pintype "passive"))
      (node (ref "C3") (pin "1") (pinfunction "1_1") (pintype "passive"))
      (node (ref "C4") (pin "2") (pinfunction "2_2") (pintype "passive"))
      (node (ref "C5") (pin "2") (pinfunction "2_2") (pintype "passive"))
      (node (ref "C6") (pin "1") (pinfunction "1_1") (pintype "passive"))
      (node (ref "C7") (pin "2") (pinfunction "2_2") (pintype "passive"))
      (node (ref "C8") (pin "1") (pinfunction "1_1") (pintype "passive"))
      (node (ref "C9") (pin "1") (pinfunction "1_1") (pintype "passive"))
      (node (ref "CM1") (pin "P$1") (pinfunction "SHIELD3_P$1") (pintype "passive"))
      (node (ref "CM1") (pin "P$2") (pinfunction "SHIELD2_P$2") (pintype "passive"))
      (node (ref "CM1") (pin "P$3") (pinfunction "SHIELD1_P$3") (pintype "passive"))
      (node (ref "CM1") (pin "P$4") (pinfunction "SHIELD_P$4") (pintype "passive"))
      (node (ref "CM2") (pin "P$1") (pinfunction "SHIELD3_P$1") (pintype "passive"))
      (node (ref "CM2") (pin "P$2") (pinfunction "SHIELD2_P$2") (pintype "passive"))
      (node (ref "CM2") (pin "P$3") (pinfunction "SHIELD1_P$3") (pintype "passive"))
      (node (ref "CM2") (pin "P$4") (pinfunction "SHIELD_P$4") (pintype "passive"))
      (node (ref "CM3") (pin "P$1") (pinfunction "SHIELD3_P$1") (pintype "passive"))
      (node (ref "CM3") (pin "P$2") (pinfunction "SHIELD2_P$2") (pintype "passive"))
      (node (ref "CM3") (pin "P$3") (pinfunction "SHIELD1_P$3") (pintype "passive"))
      (node (ref "CM3") (pin "P$4") (pinfunction "SHIELD_P$4") (pintype "passive"))
      (node (ref "D1") (pin "C") (pinfunction "C_C") (pintype "passive"))
      (node (ref "D2") (pin "C") (pinfunction "C_C") (pintype "passive"))
      (node (ref "D3") (pin "C") (pinfunction "C_C") (pintype "passive"))
      (node (ref "D5") (pin "C") (pinfunction "C_C") (pintype "passive"))
      (node (ref "J10") (pin "1") (pinfunction "1_1") (pintype "passive"))
      (node (ref "J10") (pin "10") (pinfunction "10_10") (pintype "passive"))
      (node (ref "J10") (pin "12") (pinfunction "12_12") (pintype "passive"))
      (node (ref "J10") (pin "14") (pinfunction "14_14") (pintype "passive"))
      (node (ref "J10") (pin "15") (pinfunction "15_15") (pintype "passive"))
      (node (ref "J10") (pin "16") (pinfunction "16_16") (pintype "passive"))
      (node (ref "J10") (pin "2") (pinfunction "2_2") (pintype "passive"))
      (node (ref "J10") (pin "4") (pinfunction "4_4") (pintype "passive"))
      (node (ref "J10") (pin "6") (pinfunction "6_6") (pintype "passive"))
      (node (ref "J10") (pin "8") (pinfunction "8_8") (pintype "passive"))
      (node (ref "J11") (pin "1") (pinfunction "1_1") (pintype "passive"))
      (node (ref "J11") (pin "10") (pinfunction "10_10") (pintype "passive"))
      (node (ref "J11") (pin "12") (pinfunction "12_12") (pintype "passive"))
      (node (ref "J11") (pin "14") (pinfunction "14_14") (pintype "passive"))
      (node (ref "J11") (pin "15") (pinfunction "15_15") (pintype "passive"))
      (node (ref "J11") (pin "16") (pinfunction "16_16") (pintype "passive"))
      (node (ref "J11") (pin "2") (pinfunction "2_2") (pintype "passive"))
      (node (ref "J11") (pin "4") (pinfunction "4_4") (pintype "passive"))
      (node (ref "J11") (pin "6") (pinfunction "6_6") (pintype "passive"))
      (node (ref "J11") (pin "8") (pinfunction "8_8") (pintype "passive"))
      (node (ref "J12") (pin "1") (pinfunction "1_1") (pintype "passive"))
      (node (ref "J12") (pin "10") (pinfunction "10_10") (pintype "passive"))
      (node (ref "J12") (pin "12") (pinfunction "12_12") (pintype "passive"))
      (node (ref "J12") (pin "14") (pinfunction "14_14") (pintype "passive"))
      (node (ref "J12") (pin "15") (pinfunction "15_15") (pintype "passive"))
      (node (ref "J12") (pin "16") (pinfunction "16_16") (pintype "passive"))
      (node (ref "J12") (pin "2") (pinfunction "2_2") (pintype "passive"))
      (node (ref "J12") (pin "4") (pinfunction "4_4") (pintype "passive"))
      (node (ref "J12") (pin "6") (pinfunction "6_6") (pintype "passive"))
      (node (ref "J12") (pin "8") (pinfunction "8_8") (pintype "passive"))
      (node (ref "J2") (pin "1") (pinfunction "GND_1") (pintype "bidirectional"))
      (node (ref "J2") (pin "2") (pinfunction "GND_2") (pintype "bidirectional"))
      (node (ref "J3") (pin "1") (pinfunction "GND_1") (pintype "bidirectional"))
      (node (ref "J3") (pin "2") (pinfunction "GND_2") (pintype "bidirectional"))
      (node (ref "J4") (pin "1") (pinfunction "GND_1") (pintype "bidirectional"))
      (node (ref "J4") (pin "2") (pinfunction "GND_2") (pintype "bidirectional"))
      (node (ref "J5") (pin "P$6") (pinfunction "GND_P$6") (pintype "passive"))
      (node (ref "J6") (pin "27") (pinfunction "27_27") (pintype "passive"))
      (node (ref "J6") (pin "28") (pinfunction "28_28") (pintype "passive"))
      (node (ref "J6") (pin "29") (pinfunction "29_29") (pintype "passive"))
      (node (ref "J6") (pin "30") (pinfunction "30_30") (pintype "passive"))
      (node (ref "J6") (pin "31") (pinfunction "31_31") (pintype "passive"))
      (node (ref "J6") (pin "32") (pinfunction "32_32") (pintype "passive"))
      (node (ref "J6") (pin "37") (pinfunction "37_37") (pintype "passive"))
      (node (ref "J6") (pin "38") (pinfunction "38_38") (pintype "passive"))
      (node (ref "J7") (pin "3") (pinfunction "GND_3") (pintype "passive"))
      (node (ref "J7") (pin "5") (pinfunction "GND_5") (pintype "passive"))
      (node (ref "J7") (pin "9") (pinfunction "GNDDET_9") (pintype "passive"))
      (node (ref "J8") (pin "3") (pinfunction "VSS1_3") (pintype "power_in"))
      (node (ref "J8") (pin "6") (pinfunction "VSS2_6") (pintype "power_in"))
      (node (ref "J8") (pin "SH@1") (pinfunction "SH_SH@1") (pintype "bidirectional"))
      (node (ref "J8") (pin "SH@2") (pinfunction "SH_SH@2") (pintype "bidirectional"))
      (node (ref "J9") (pin "1") (pinfunction "1_1") (pintype "passive"))
      (node (ref "J9") (pin "10") (pinfunction "10_10") (pintype "passive"))
      (node (ref "J9") (pin "12") (pinfunction "12_12") (pintype "passive"))
      (node (ref "J9") (pin "14") (pinfunction "14_14") (pintype "passive"))
      (node (ref "J9") (pin "15") (pinfunction "15_15") (pintype "passive"))
      (node (ref "J9") (pin "16") (pinfunction "16_16") (pintype "passive"))
      (node (ref "J9") (pin "2") (pinfunction "2_2") (pintype "passive"))
      (node (ref "J9") (pin "4") (pinfunction "4_4") (pintype "passive"))
      (node (ref "J9") (pin "6") (pinfunction "6_6") (pintype "passive"))
      (node (ref "J9") (pin "8") (pinfunction "8_8") (pintype "passive"))
      (node (ref "JP2") (pin "10") (pinfunction "10_10") (pintype "passive"))
      (node (ref "JP2") (pin "7") (pinfunction "7_7") (pintype "passive"))
      (node (ref "JP2") (pin "8") (pinfunction "8_8") (pintype "passive"))
      (node (ref "JP2") (pin "9") (pinfunction "9_9") (pintype "passive"))
      (node (ref "R10") (pin "1") (pinfunction "1_1") (pintype "passive"))
      (node (ref "R17") (pin "1") (pinfunction "1_1") (pintype "passive"))
      (node (ref "R36") (pin "1") (pinfunction "1_1") (pintype "passive"))
      (node (ref "R6") (pin "1") (pinfunction "1_1") (pintype "passive"))
      (node (ref "R9") (pin "1") (pinfunction "1_1") (pintype "passive"))
      (node (ref "U1") (pin "4") (pinfunction "GND_4") (pintype "power_in"))
      (node (ref "U2") (pin "2") (pinfunction "GND_2") (pintype "power_in"))
      (node (ref "U3") (pin "2") (pinfunction "GND_2") (pintype "power_in"))
      (node (ref "U4") (pin "1") (pinfunction "GND_1") (pintype "bidirectional"))
      (node (ref "U4") (pin "THERMAL") (pinfunction "GND_THERMAL") (pintype "bidirectional"))
      (node (ref "U5") (pin "1") (pinfunction "GND_1") (pintype "power_in"))
      (node (ref "U5") (pin "11") (pinfunction "GND_11") (pintype "power_in"))
      (node (ref "U5") (pin "12") (pinfunction "GND_12") (pintype "power_in"))
      (node (ref "U5") (pin "16") (pinfunction "GND_16") (pintype "power_in"))
      (node (ref "U5") (pin "6") (pinfunction "LBO_6") (pintype "open_collector"))
      (node (ref "U5") (pin "7") (pinfunction "LBI_7") (pintype "input"))
      (node (ref "U5") (pin "9") (pinfunction "GND_9") (pintype "power_in"))
      (node (ref "U5") (pin "PAD") (pinfunction "GND_PAD") (pintype "power_in"))
      (node (ref "U6") (pin "2") (pinfunction "GND_2") (pintype "power_in"))
      (node (ref "U6") (pin "5") (pinfunction "SET1_5") (pintype "input"))
      (node (ref "U6") (pin "6") (pinfunction "SET2_6") (pintype "input"))
      (node (ref "U7") (pin "12") (pinfunction "VSSA_12") (pintype "power_in"))
      (node (ref "U7") (pin "18") (pinfunction "VSS_18") (pintype "power_in"))
      (node (ref "U7") (pin "31") (pinfunction "VSS_31") (pintype "power_in"))
      (node (ref "U7") (pin "47") (pinfunction "VSS_47") (pintype "power_in"))
      (node (ref "U7") (pin "63") (pinfunction "VSS_63") (pintype "power_in"))
      (node (ref "X1") (pin "2") (pinfunction "SHIELD_2") (pintype "power_in"))
      (node (ref "X1") (pin "4") (pinfunction "SHIELD_4") (pintype "power_in"))
    )
    (net (code "27") (name "MMC_CS") (class "Default")
      (node (ref "J8") (pin "1") (pinfunction "CD/DAT3_1") (pintype "bidirectional"))
      (node (ref "U7") (pin "40") (pinfunction "PC9_40") (pintype "bidirectional"))
    )
    (net (code "28") (name "MMC_PWR") (class "Default")
      (node (ref "Q1") (pin "3") (pinfunction "G_3") (pintype "passive"))
      (node (ref "R18") (pin "2") (pinfunction "2_2") (pintype "passive"))
      (node (ref "U7") (pin "39") (pinfunction "PC8_39") (pintype "bidirectional"))
    )
    (net (code "29") (name "MMC_VDD") (class "Default")
      (node (ref "C20") (pin "1") (pinfunction "1_1") (pintype "passive"))
      (node (ref "J8") (pin "4") (pinfunction "VDD_4") (pintype "power_in"))
      (node (ref "Q1") (pin "1") (pinfunction "D_1") (pintype "passive"))
      (node (ref "Q1") (pin "2") (pinfunction "D_2") (pintype "passive"))
      (node (ref "Q1") (pin "5") (pinfunction "D_5") (pintype "passive"))
      (node (ref "Q1") (pin "6") (pinfunction "D_6") (pintype "passive"))
    )
    (net (code "30") (name "NRST") (class "Default")
      (node (ref "J7") (pin "10") (pinfunction "~{RESET}_10") (pintype "passive"))
      (node (ref "TP2") (pin "1") (pinfunction "1_1") (pintype "passive"))
      (node (ref "U7") (pin "7") (pinfunction "NRST_7") (pintype "bidirectional"))
    )
    (net (code "31") (name "Net-(CM1-CENTER)") (class "Default")
      (node (ref "CM1") (pin "RF") (pinfunction "CENTER_RF") (pintype "passive"))
      (node (ref "J2") (pin "FEED") (pinfunction "SIGNAL_FEED") (pintype "bidirectional"))
    )
    (net (code "32") (name "Net-(CM2-CENTER)") (class "Default")
      (node (ref "CM2") (pin "RF") (pinfunction "CENTER_RF") (pintype "passive"))
      (node (ref "J3") (pin "FEED") (pinfunction "SIGNAL_FEED") (pintype "bidirectional"))
    )
    (net (code "33") (name "Net-(CM3-CENTER)") (class "Default")
      (node (ref "CM3") (pin "RF") (pinfunction "CENTER_RF") (pintype "passive"))
      (node (ref "J4") (pin "FEED") (pinfunction "SIGNAL_FEED") (pintype "bidirectional"))
    )
    (net (code "34") (name "Net-(D1-PadA)") (class "Default")
      (node (ref "D1") (pin "A") (pinfunction "A_A") (pintype "passive"))
      (node (ref "R1") (pin "1") (pinfunction "1_1") (pintype "passive"))
    )
    (net (code "35") (name "Net-(D2-PadA)") (class "Default")
      (node (ref "D2") (pin "A") (pinfunction "A_A") (pintype "passive"))
      (node (ref "R2") (pin "1") (pinfunction "1_1") (pintype "passive"))
    )
    (net (code "36") (name "Net-(D3-PadA)") (class "Default")
      (node (ref "D3") (pin "A") (pinfunction "A_A") (pintype "passive"))
      (node (ref "R3") (pin "1") (pinfunction "1_1") (pintype "passive"))
    )
    (net (code "37") (name "Net-(D4-PadA)") (class "Default")
      (node (ref "D4") (pin "A") (pinfunction "A_A") (pintype "passive"))
      (node (ref "R27") (pin "1") (pinfunction "1_1") (pintype "passive"))
    )
    (net (code "38") (name "Net-(D5-PadA)") (class "Default")
      (node (ref "D5") (pin "A") (pinfunction "A_A") (pintype "passive"))
      (node (ref "R4") (pin "1") (pinfunction "1_1") (pintype "passive"))
    )
    (net (code "39") (name "Net-(D7-C)") (class "Default")
      (node (ref "D7") (pin "1") (pinfunction "C_1") (pintype "passive"))
      (node (ref "R19") (pin "2") (pinfunction "2_2") (pintype "passive"))
    )
    (net (code "40") (name "Net-(J5-VCC)") (class "Default")
      (node (ref "J5") (pin "P$4") (pinfunction "VCC_P$4") (pintype "passive"))
      (node (ref "JP8") (pin "2") (pinfunction "2_2") (pintype "passive"))
    )
    (net (code "41") (name "Net-(L2-Pad1)") (class "Default")
      (node (ref "L2") (pin "1") (pinfunction "1_1") (pintype "passive"))
      (node (ref "U5") (pin "14") (pinfunction "SW_14") (pintype "output"))
      (node (ref "U5") (pin "15") (pinfunction "SW_15") (pintype "output"))
    )
    (net (code "42") (name "Net-(U1-IN)") (class "Default")
      (node (ref "C5") (pin "1") (pinfunction "1_1") (pintype "passive"))
      (node (ref "R12") (pin "1") (pinfunction "1_1") (pintype "passive"))
      (node (ref "U1") (pin "1") (pinfunction "IN_2_1") (pintype "power_in"))
      (node (ref "U1") (pin "2") (pinfunction "IN_2") (pintype "power_in"))
    )
    (net (code "43") (name "Net-(U4-EN{slash}UVLO)") (class "Default")
      (node (ref "R5") (pin "1") (pinfunction "1_1") (pintype "passive"))
      (node (ref "R9") (pin "2") (pinfunction "2_2") (pintype "passive"))
      (node (ref "U4") (pin "3") (pinfunction "EN/UVLO_3") (pintype "bidirectional"))
    )
    (net (code "44") (name "Net-(U4-~{FLT})") (class "Default")
      (node (ref "TP1") (pin "1") (pinfunction "1_1") (pintype "passive"))
      (node (ref "U4") (pin "6") (pinfunction "~{FLT}_6") (pintype "bidirectional"))
    )
    (net (code "45") (name "Net-(U5-PG)") (class "Default")
      (node (ref "TP16") (pin "1") (pinfunction "1_1") (pintype "passive"))
      (node (ref "U5") (pin "13") (pinfunction "PG_13") (pintype "open_collector"))
    )
    (net (code "46") (name "Net-(U5-SYNC)") (class "Default")
      (node (ref "R10") (pin "2") (pinfunction "2_2") (pintype "passive"))
      (node (ref "R7") (pin "1") (pinfunction "1_1") (pintype "passive"))
      (node (ref "TP19") (pin "1") (pinfunction "1_1") (pintype "passive"))
      (node (ref "U5") (pin "5") (pinfunction "SYNC_5") (pintype "input"))
    )
    (net (code "47") (name "Net-(U6-SET0)") (class "Default")
      (node (ref "C15") (pin "1") (pinfunction "1_1") (pintype "passive"))
      (node (ref "C18") (pin "1") (pinfunction "1_1") (pintype "passive"))
      (node (ref "R19") (pin "1") (pinfunction "1_1") (pintype "passive"))
      (node (ref "U6") (pin "4") (pinfunction "SET0_4") (pintype "input"))
      (node (ref "U6") (pin "8") (pinfunction "VCC_8") (pintype "power_in"))
    )
    (net (code "48") (name "Net-(U7-BOOT0)") (class "Default")
      (node (ref "R17") (pin "2") (pinfunction "2_2") (pintype "passive"))
      (node (ref "TP15") (pin "1") (pinfunction "1_1") (pintype "passive"))
      (node (ref "U7") (pin "60") (pinfunction "BOOT0_60") (pintype "bidirectional"))
    )
    (net (code "49") (name "Net-(U7-PH0-OSC_IN)") (class "Default")
      (node (ref "C16") (pin "1") (pinfunction "1_1") (pintype "passive"))
      (node (ref "U7") (pin "5") (pinfunction "PH0-OSC_IN_5") (pintype "bidirectional"))
      (node (ref "X1") (pin "1") (pinfunction "1_1") (pintype "passive"))
    )
    (net (code "50") (name "Net-(U7-PH1-OSC_OUT)") (class "Default")
      (node (ref "C11") (pin "1") (pinfunction "1_1") (pintype "passive"))
      (node (ref "U7") (pin "6") (pinfunction "PH1-OSC_OUT_6") (pintype "bidirectional"))
      (node (ref "X1") (pin "3") (pinfunction "2_3") (pintype "passive"))
    )
    (net (code "51") (name "OPD_ISET") (class "Default")
      (node (ref "R24") (pin "1") (pinfunction "1_1") (pintype "passive"))
      (node (ref "R36") (pin "2") (pinfunction "2_2") (pintype "passive"))
      (node (ref "TP14") (pin "1") (pinfunction "1_1") (pintype "passive"))
      (node (ref "U1") (pin "5") (pinfunction "SET_5") (pintype "input"))
    )
    (net (code "52") (name "OPD_ISET_IN") (class "Default")
      (node (ref "R24") (pin "2") (pinfunction "2_2") (pintype "passive"))
      (node (ref "U7") (pin "27") (pinfunction "PB1_27") (pintype "bidirectional"))
    )
    (net (code "53") (name "OPD_PWR") (class "Default")
      (node (ref "C4") (pin "1") (pinfunction "1_1") (pintype "passive"))
      (node (ref "J6") (pin "15") (pinfunction "15_15") (pintype "passive"))
      (node (ref "J6") (pin "16") (pinfunction "16_16") (pintype "passive"))
      (node (ref "JP1") (pin "5") (pinfunction "5_5") (pintype "passive"))
      (node (ref "JP1") (pin "6") (pinfunction "6_6") (pintype "passive"))
      (node (ref "R11") (pin "1") (pinfunction "1_1") (pintype "passive"))
      (node (ref "R4") (pin "2") (pinfunction "2_2") (pintype "passive"))
      (node (ref "R8") (pin "1") (pinfunction "1_1") (pintype "passive"))
      (node (ref "U1") (pin "7") (pinfunction "OUT_2_7") (pintype "power_in"))
      (node (ref "U1") (pin "8") (pinfunction "OUT_8") (pintype "power_in"))
    )
    (net (code "54") (name "OPD_SCL") (class "Default")
      (node (ref "J6") (pin "13") (pinfunction "13_13") (pintype "passive"))
      (node (ref "J6") (pin "14") (pinfunction "14_14") (pintype "passive"))
      (node (ref "JP1") (pin "3") (pinfunction "3_3") (pintype "passive"))
      (node (ref "JP1") (pin "4") (pinfunction "4_4") (pintype "passive"))
      (node (ref "R8") (pin "2") (pinfunction "2_2") (pintype "passive"))
      (node (ref "U7") (pin "61") (pinfunction "PB8_61") (pintype "bidirectional"))
    )
    (net (code "55") (name "OPD_SDA") (class "Default")
      (node (ref "J6") (pin "11") (pinfunction "11_11") (pintype "passive"))
      (node (ref "J6") (pin "12") (pinfunction "12_12") (pintype "passive"))
      (node (ref "JP1") (pin "1") (pinfunction "1_1") (pintype "passive"))
      (node (ref "JP1") (pin "2") (pinfunction "2_2") (pintype "passive"))
      (node (ref "R11") (pin "2") (pinfunction "2_2") (pintype "passive"))
      (node (ref "U7") (pin "62") (pinfunction "PB9_62") (pintype "bidirectional"))
    )
    (net (code "56") (name "OPD_~{FAULT}") (class "Default")
      (node (ref "R16") (pin "1") (pinfunction "1_1") (pintype "passive"))
      (node (ref "TP8") (pin "1") (pinfunction "1_1") (pintype "passive"))
      (node (ref "U1") (pin "6") (pinfunction "~{FAULT}_6") (pintype "output"))
      (node (ref "U7") (pin "55") (pinfunction "PB3_55") (pintype "bidirectional"))
    )
    (net (code "57") (name "OSC32_IN") (class "Default")
      (node (ref "U7") (pin "3") (pinfunction "PC14-OSC32_IN_3") (pintype "bidirectional"))
    )
    (net (code "58") (name "OSC32_OUT") (class "Default")
      (node (ref "U7") (pin "4") (pinfunction "PC15-OSC32_OUT_4") (pintype "bidirectional"))
    )
    (net (code "59") (name "PA1") (class "Default")
      (node (ref "TP5") (pin "1") (pinfunction "1_1") (pintype "passive"))
      (node (ref "U7") (pin "15") (pinfunction "PA1_15") (pintype "bidirectional"))
    )
    (net (code "60") (name "PA15") (class "Default")
      (node (ref "TP6") (pin "1") (pinfunction "1_1") (pintype "passive"))
      (node (ref "U7") (pin "50") (pinfunction "PA15_50") (pintype "bidirectional"))
    )
    (net (code "61") (name "PB10") (class "Default")
      (node (ref "TP4") (pin "1") (pinfunction "1_1") (pintype "passive"))
      (node (ref "U7") (pin "29") (pinfunction "PB10_29") (pintype "bidirectional"))
    )
    (net (code "62") (name "PB12") (class "Default")
      (node (ref "JP11") (pin "1") (pinfunction "1_1") (pintype "passive"))
      (node (ref "U7") (pin "33") (pinfunction "PB12_33") (pintype "bidirectional"))
    )
    (net (code "63") (name "PC0") (class "Default")
      (node (ref "JP11") (pin "9") (pinfunction "9_9") (pintype "passive"))
      (node (ref "U7") (pin "8") (pinfunction "PC0_8") (pintype "bidirectional"))
    )
    (net (code "64") (name "PC1") (class "Default")
      (node (ref "JP11") (pin "10") (pinfunction "10_10") (pintype "passive"))
      (node (ref "U7") (pin "9") (pinfunction "PC1_9") (pintype "bidirectional"))
    )
    (net (code "65") (name "PC2") (class "Default")
      (node (ref "JP11") (pin "8") (pinfunction "8_8") (pintype "passive"))
      (node (ref "U7") (pin "10") (pinfunction "PC2_10") (pintype "bidirectional"))
    )
    (net (code "66") (name "PC3") (class "Default")
      (node (ref "JP11") (pin "6") (pinfunction "6_6") (pintype "passive"))
      (node (ref "U7") (pin "11") (pinfunction "PC3_11") (pintype "bidirectional"))
    )
    (net (code "67") (name "PC4") (class "Default")
      (node (ref "JP11") (pin "4") (pinfunction "4_4") (pintype "passive"))
      (node (ref "U7") (pin "24") (pinfunction "PC4_24") (pintype "bidirectional"))
    )
    (net (code "68") (name "PC5") (class "Default")
      (node (ref "JP11") (pin "2") (pinfunction "2_2") (pintype "passive"))
      (node (ref "U7") (pin "25") (pinfunction "PC5_25") (pintype "bidirectional"))
    )
    (net (code "69") (name "PC13") (class "Default")
      (node (ref "TP12") (pin "1") (pinfunction "1_1") (pintype "passive"))
      (node (ref "U7") (pin "2") (pinfunction "PC13_2") (pintype "bidirectional"))
    )
    (net (code "70") (name "PD2") (class "Default")
      (node (ref "TP7") (pin "1") (pinfunction "1_1") (pintype "passive"))
      (node (ref "U7") (pin "54") (pinfunction "PD2_54") (pintype "bidirectional"))
    )
    (net (code "71") (name "RADIO1_CS") (class "Default")
      (node (ref "J12") (pin "5") (pinfunction "5_5") (pintype "passive"))
      (node (ref "U7") (pin "37") (pinfunction "PC6_37") (pintype "bidirectional"))
    )
    (net (code "72") (name "RADIO1_IRQ") (class "Default")
      (node (ref "J12") (pin "13") (pinfunction "13_13") (pintype "passive"))
      (node (ref "U7") (pin "20") (pinfunction "PA4_20") (pintype "bidirectional"))
    )
    (net (code "73") (name "RADIO1_SYSCLK") (class "Default")
      (node (ref "J12") (pin "3") (pinfunction "3_3") (pintype "passive"))
      (node (ref "TP21") (pin "1") (pinfunction "1_1") (pintype "passive"))
    )
    (net (code "74") (name "RADIO2_CS") (class "Default")
      (node (ref "J10") (pin "5") (pinfunction "5_5") (pintype "passive"))
      (node (ref "U7") (pin "38") (pinfunction "PC7_38") (pintype "bidirectional"))
    )
    (net (code "75") (name "RADIO2_IRQ") (class "Default")
      (node (ref "J10") (pin "13") (pinfunction "13_13") (pintype "passive"))
      (node (ref "U7") (pin "41") (pinfunction "PA8_41") (pintype "bidirectional"))
    )
    (net (code "76") (name "RADIO2_SYSCLK") (class "Default")
      (node (ref "J10") (pin "3") (pinfunction "3_3") (pintype "passive"))
      (node (ref "TP9") (pin "1") (pinfunction "1_1") (pintype "passive"))
    )
    (net (code "77") (name "SPARE1") (class "Default")
      (node (ref "J6") (pin "10") (pinfunction "10_10") (pintype "passive"))
      (node (ref "J6") (pin "9") (pinfunction "9_9") (pintype "passive"))
      (node (ref "JP2") (pin "5") (pinfunction "5_5") (pintype "passive"))
    )
    (net (code "78") (name "SPARE2") (class "Default")
      (node (ref "J6") (pin "7") (pinfunction "7_7") (pintype "passive"))
      (node (ref "J6") (pin "8") (pinfunction "8_8") (pintype "passive"))
      (node (ref "JP2") (pin "4") (pinfunction "4_4") (pintype "passive"))
    )
    (net (code "79") (name "SPARE3") (class "Default")
      (node (ref "J6") (pin "5") (pinfunction "5_5") (pintype "passive"))
      (node (ref "J6") (pin "6") (pinfunction "6_6") (pintype "passive"))
      (node (ref "JP2") (pin "3") (pinfunction "3_3") (pintype "passive"))
    )
    (net (code "80") (name "SPARE4") (class "Default")
      (node (ref "J6") (pin "3") (pinfunction "3_3") (pintype "passive"))
      (node (ref "J6") (pin "4") (pinfunction "4_4") (pintype "passive"))
      (node (ref "JP2") (pin "2") (pinfunction "2_2") (pintype "passive"))
    )
    (net (code "81") (name "SPARE5") (class "Default")
      (node (ref "J6") (pin "1") (pinfunction "1_1") (pintype "passive"))
      (node (ref "J6") (pin "2") (pinfunction "2_2") (pintype "passive"))
      (node (ref "JP2") (pin "1") (pinfunction "1_1") (pintype "passive"))
    )
    (net (code "82") (name "SPI1_MISO") (class "Default")
      (node (ref "J10") (pin "9") (pinfunction "9_9") (pintype "passive"))
      (node (ref "J12") (pin "9") (pinfunction "9_9") (pintype "passive"))
      (node (ref "TP22") (pin "1") (pinfunction "1_1") (pintype "passive"))
      (node (ref "U7") (pin "22") (pinfunction "PA6_22") (pintype "bidirectional"))
    )
    (net (code "83") (name "SPI1_MOSI") (class "Default")
      (node (ref "J10") (pin "11") (pinfunction "11_11") (pintype "passive"))
      (node (ref "J12") (pin "11") (pinfunction "11_11") (pintype "passive"))
      (node (ref "TP18") (pin "1") (pinfunction "1_1") (pintype "passive"))
      (node (ref "U7") (pin "23") (pinfunction "PA7_23") (pintype "bidirectional"))
    )
    (net (code "84") (name "SPI1_SCK") (class "Default")
      (node (ref "J10") (pin "7") (pinfunction "7_7") (pintype "passive"))
      (node (ref "J12") (pin "7") (pinfunction "7_7") (pintype "passive"))
      (node (ref "TP23") (pin "1") (pinfunction "1_1") (pintype "passive"))
      (node (ref "U7") (pin "21") (pinfunction "PA5_21") (pintype "bidirectional"))
    )
    (net (code "85") (name "SPI2_MISO") (class "Default")
      (node (ref "JP11") (pin "5") (pinfunction "5_5") (pintype "passive"))
      (node (ref "U7") (pin "35") (pinfunction "PB14_35") (pintype "bidirectional"))
    )
    (net (code "86") (name "SPI2_MOSI") (class "Default")
      (node (ref "JP11") (pin "7") (pinfunction "7_7") (pintype "passive"))
      (node (ref "U7") (pin "36") (pinfunction "PB15_36") (pintype "bidirectional"))
    )
    (net (code "87") (name "SPI2_SCK") (class "Default")
      (node (ref "JP11") (pin "3") (pinfunction "3_3") (pintype "passive"))
      (node (ref "U7") (pin "34") (pinfunction "PB13_34") (pintype "bidirectional"))
    )
    (net (code "88") (name "SPI3_MISO") (class "Default")
      (node (ref "J8") (pin "7") (pinfunction "DAT0_7") (pintype "bidirectional"))
      (node (ref "U7") (pin "52") (pinfunction "PC11_52") (pintype "bidirectional"))
    )
    (net (code "89") (name "SPI3_MOSI") (class "Default")
      (node (ref "J8") (pin "2") (pinfunction "CMD_2") (pintype "bidirectional"))
      (node (ref "U7") (pin "53") (pinfunction "PC12_53") (pintype "bidirectional"))
    )
    (net (code "90") (name "SPI3_SCK") (class "Default")
      (node (ref "J8") (pin "5") (pinfunction "CLK_5") (pintype "bidirectional"))
      (node (ref "U7") (pin "51") (pinfunction "PC10_51") (pintype "bidirectional"))
    )
    (net (code "91") (name "SWCLK") (class "Default")
      (node (ref "J7") (pin "4") (pinfunction "SWDCLK/TCK_4") (pintype "passive"))
      (node (ref "U7") (pin "49") (pinfunction "PA14_49") (pintype "bidirectional"))
    )
    (net (code "92") (name "SWDIO") (class "Default")
      (node (ref "J7") (pin "2") (pinfunction "SWDIO/TMS_2") (pintype "passive"))
      (node (ref "U7") (pin "46") (pinfunction "PA13_46") (pintype "bidirectional"))
    )
    (net (code "93") (name "USART2_RX") (class "Default")
      (node (ref "J5") (pin "P$2") (pinfunction "TXO_P$2") (pintype "passive"))
      (node (ref "U7") (pin "17") (pinfunction "PA3_17") (pintype "bidirectional"))
    )
    (net (code "94") (name "USART2_TX") (class "Default")
      (node (ref "J5") (pin "P$3") (pinfunction "RXI_P$3") (pintype "passive"))
      (node (ref "U7") (pin "16") (pinfunction "PA2_16") (pintype "bidirectional"))
    )
    (net (code "95") (name "VBUS") (class "Default")
      (node (ref "C1") (pin "1") (pinfunction "1_1") (pintype "passive"))
      (node (ref "J6") (pin "21") (pinfunction "21_21") (pintype "passive"))
      (node (ref "J6") (pin "22") (pinfunction "22_22") (pintype "passive"))
      (node (ref "J6") (pin "23") (pinfunction "23_23") (pintype "passive"))
      (node (ref "J6") (pin "24") (pinfunction "24_24") (pintype "passive"))
      (node (ref "J6") (pin "25") (pinfunction "25_25") (pintype "passive"))
      (node (ref "J6") (pin "26") (pinfunction "26_26") (pintype "passive"))
      (node (ref "JP10") (pin "1") (pinfunction "1_1") (pintype "passive"))
      (node (ref "JP10") (pin "2") (pinfunction "2_2") (pintype "passive"))
      (node (ref "JP10") (pin "3") (pinfunction "3_3") (pintype "passive"))
      (node (ref "JP10") (pin "4") (pinfunction "4_4") (pintype "passive"))
      (node (ref "R5") (pin "2") (pinfunction "2_2") (pintype "passive"))
      (node (ref "U4") (pin "4") (pinfunction "VIN_4") (pintype "power_in"))
    )
    (net (code "96") (name "VBUSP") (class "Default")
      (node (ref "C10") (pin "1") (pinfunction "1_1") (pintype "passive"))
      (node (ref "C7") (pin "1") (pinfunction "1_1") (pintype "passive"))
      (node (ref "JP3") (pin "1") (pinfunction "1_1") (pintype "passive"))
      (node (ref "JP3") (pin "2") (pinfunction "2_2") (pintype "passive"))
      (node (ref "JP3") (pin "3") (pinfunction "3_3") (pintype "passive"))
      (node (ref "JP8") (pin "1") (pinfunction "1_1") (pintype "passive"))
      (node (ref "R1") (pin "2") (pinfunction "2_2") (pintype "passive"))
      (node (ref "R7") (pin "2") (pinfunction "2_2") (pintype "passive"))
      (node (ref "TP20") (pin "1") (pinfunction "1_1") (pintype "passive"))
      (node (ref "U4") (pin "5") (pinfunction "VOUT_5") (pintype "power_in"))
      (node (ref "U5") (pin "2") (pinfunction "VIN_2") (pintype "power_in"))
      (node (ref "U5") (pin "3") (pinfunction "VIN_3") (pintype "power_in"))
      (node (ref "U5") (pin "4") (pinfunction "EN_4") (pintype "input"))
      (node (ref "U5") (pin "8") (pinfunction "VIN_8") (pintype "power_in"))
    )
    (net (code "97") (name "VCAP") (class "Default")
      (node (ref "C14") (pin "1") (pinfunction "1_1") (pintype "passive"))
      (node (ref "U7") (pin "30") (pinfunction "VCAP_1_30") (pintype "bidirectional"))
    )
    (net (code "98") (name "WDT") (class "Default")
      (node (ref "R3") (pin "2") (pinfunction "2_2") (pintype "passive"))
      (node (ref "TP3") (pin "1") (pinfunction "1_1") (pintype "passive"))
      (node (ref "U6") (pin "1") (pinfunction "WDI_1") (pintype "input"))
      (node (ref "U7") (pin "14") (pinfunction "PA0_14") (pintype "bidirectional"))
    )
    (net (code "99") (name "unconnected-(J5-CTS-PadP$5)") (class "Default")
      (node (ref "J5") (pin "P$5") (pinfunction "CTS_P$5") (pintype "passive"))
    )
    (net (code "100") (name "unconnected-(J5-DTR-PadP$1)") (class "Default")
      (node (ref "J5") (pin "P$1") (pinfunction "DTR_P$1") (pintype "passive"))
    )
    (net (code "101") (name "unconnected-(J7-NC{slash}TDI-Pad8)") (class "Default")
      (node (ref "J7") (pin "8") (pinfunction "NC/TDI_8") (pintype "passive"))
    )
    (net (code "102") (name "unconnected-(J7-SWO{slash}TDO-Pad6)") (class "Default")
      (node (ref "J7") (pin "6") (pinfunction "SWO/TDO_6") (pintype "passive"))
    )
    (net (code "103") (name "unconnected-(J8-DAT1-Pad8)") (class "Default")
      (node (ref "J8") (pin "8") (pinfunction "DAT1_8") (pintype "bidirectional"))
    )
    (net (code "104") (name "unconnected-(J8-DAT2-Pad9)") (class "Default")
      (node (ref "J8") (pin "9") (pinfunction "DAT2_9") (pintype "bidirectional"))
    )
    (net (code "105") (name "unconnected-(J8-PadCD)") (class "Default")
      (node (ref "J8") (pin "CD") (pinfunction "CD_CD") (pintype "bidirectional"))
    )
    (net (code "106") (name "unconnected-(J8-PadWP)") (class "Default")
      (node (ref "J8") (pin "WP") (pinfunction "WP_WP") (pintype "bidirectional"))
    )
    (net (code "107") (name "unconnected-(J9-Pad5)") (class "Default")
      (node (ref "J9") (pin "5") (pinfunction "5_5") (pintype "passive"))
    )
    (net (code "108") (name "unconnected-(J9-Pad7)") (class "Default")
      (node (ref "J9") (pin "7") (pinfunction "7_7") (pintype "passive"))
    )
    (net (code "109") (name "unconnected-(J9-Pad9)") (class "Default")
      (node (ref "J9") (pin "9") (pinfunction "9_9") (pintype "passive"))
    )
    (net (code "110") (name "unconnected-(J9-Pad11)") (class "Default")
      (node (ref "J9") (pin "11") (pinfunction "11_11") (pintype "passive"))
    )
    (net (code "111") (name "unconnected-(J11-Pad5)") (class "Default")
      (node (ref "J11") (pin "5") (pinfunction "5_5") (pintype "passive"))
    )
    (net (code "112") (name "unconnected-(J11-Pad7)") (class "Default")
      (node (ref "J11") (pin "7") (pinfunction "7_7") (pintype "passive"))
    )
    (net (code "113") (name "unconnected-(J11-Pad9)") (class "Default")
      (node (ref "J11") (pin "9") (pinfunction "9_9") (pintype "passive"))
    )
    (net (code "114") (name "unconnected-(J11-Pad11)") (class "Default")
      (node (ref "J11") (pin "11") (pinfunction "11_11") (pintype "passive"))
    )
    (net (code "115") (name "unconnected-(JP2-Pad6)") (class "Default")
      (node (ref "JP2") (pin "6") (pinfunction "6_6") (pintype "passive"))
    )
    (net (code "116") (name "unconnected-(U4-DV{slash}DT-Pad2)") (class "Default")
      (node (ref "U4") (pin "2") (pinfunction "DV/DT_2") (pintype "bidirectional"))
    )
    (net (code "117") (name "unconnected-(U4-OVLO-Pad8)") (class "Default")
      (node (ref "U4") (pin "8") (pinfunction "OVLO_8") (pintype "bidirectional"))
    )
    (net (code "118") (name "unconnected-(U6-NC-Pad3)") (class "Default")
      (node (ref "U6") (pin "3") (pinfunction "NC_3") (pintype "no_connect"))
    )
    (net (code "119") (name "~{OPD_ENABLE}") (class "Default")
      (node (ref "D4") (pin "C") (pinfunction "C_C") (pintype "passive"))
      (node (ref "TP13") (pin "1") (pinfunction "1_1") (pintype "passive"))
      (node (ref "U1") (pin "3") (pinfunction "~{ON}_3") (pintype "input"))
      (node (ref "U7") (pin "28") (pinfunction "PB2_28") (pintype "bidirectional"))
    )
    (net (code "120") (name "~{SD}") (class "Default")
      (node (ref "J6") (pin "39") (pinfunction "39_39") (pintype "passive"))
      (node (ref "J6") (pin "40") (pinfunction "40_40") (pintype "passive"))
      (node (ref "JP10") (pin "10") (pinfunction "10_10") (pintype "passive"))
      (node (ref "JP10") (pin "9") (pinfunction "9_9") (pintype "passive"))
      (node (ref "R13") (pin "2") (pinfunction "2_2") (pintype "passive"))
      (node (ref "U6") (pin "7") (pinfunction "~{WDO}_7") (pintype "output"))
    )
  )
)
